# Cubesat_Potencia_Controle-rev3.net
KiCad netlist of a schematic drawn in EAGLE
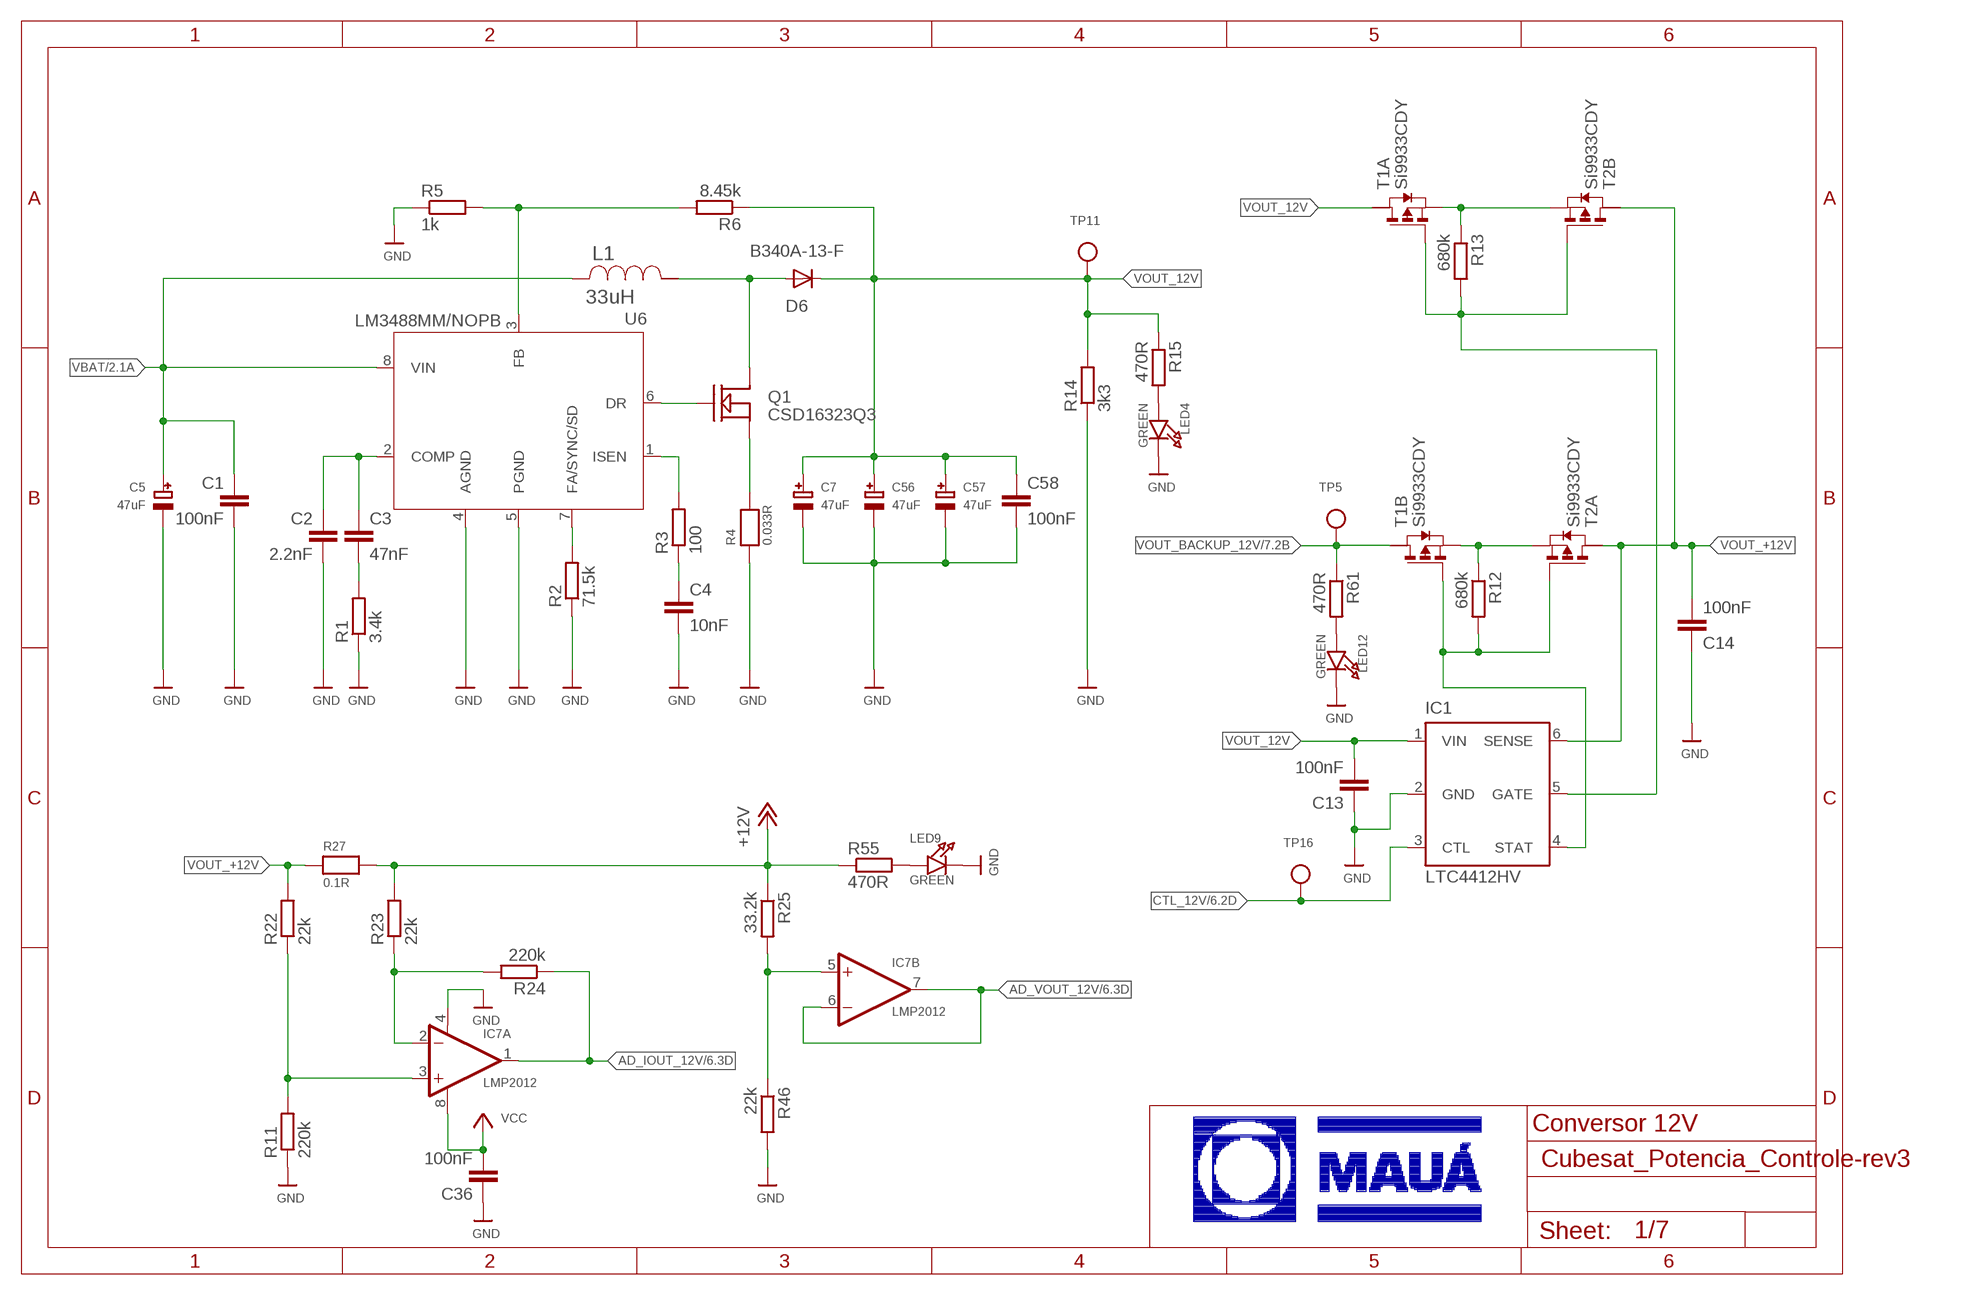
[diagram p0: schematic, sheet 1]
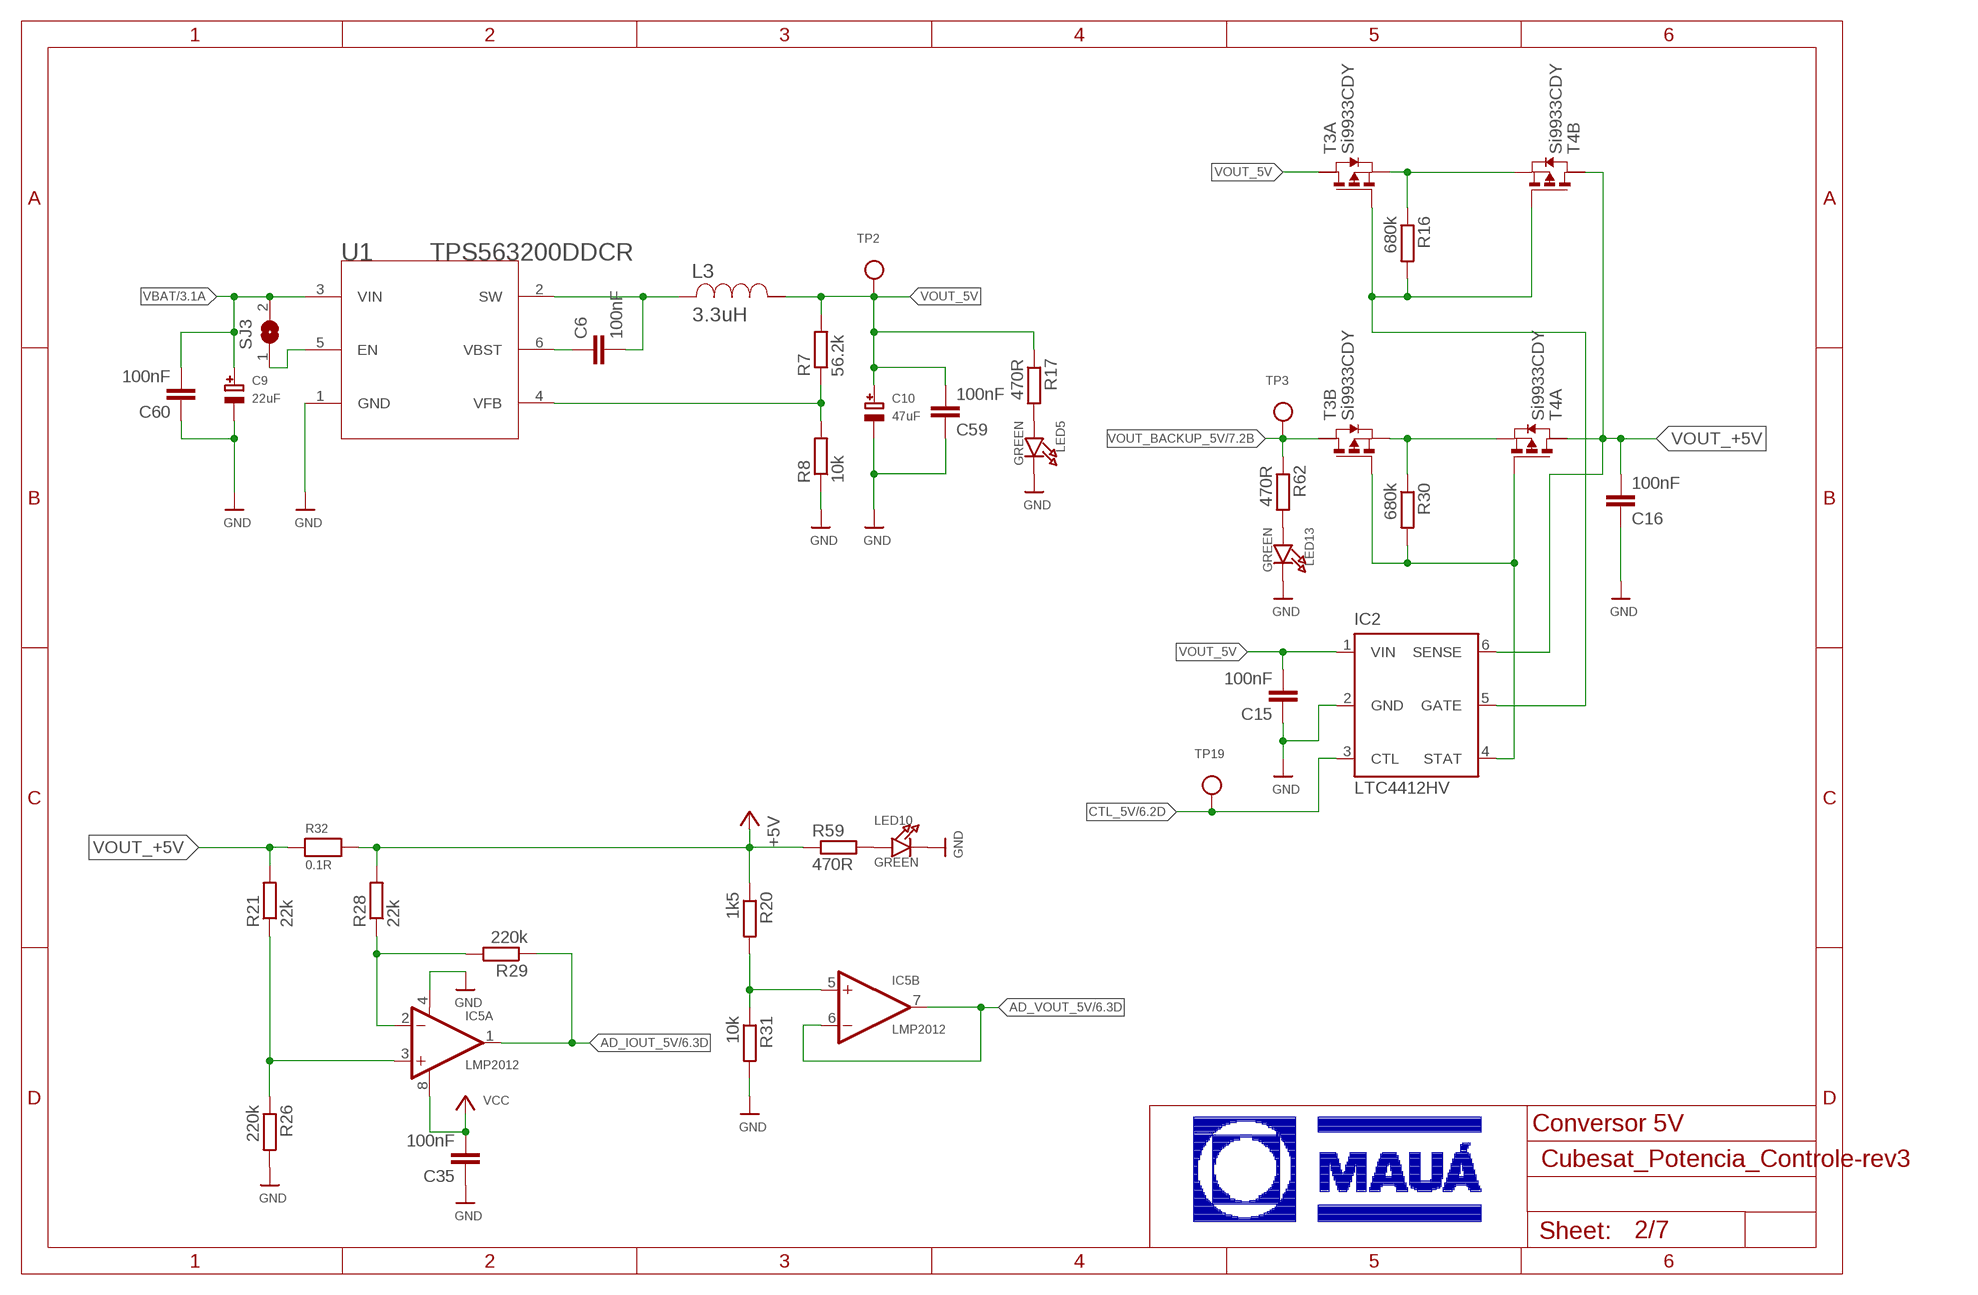
[diagram p1: schematic, sheet 2]
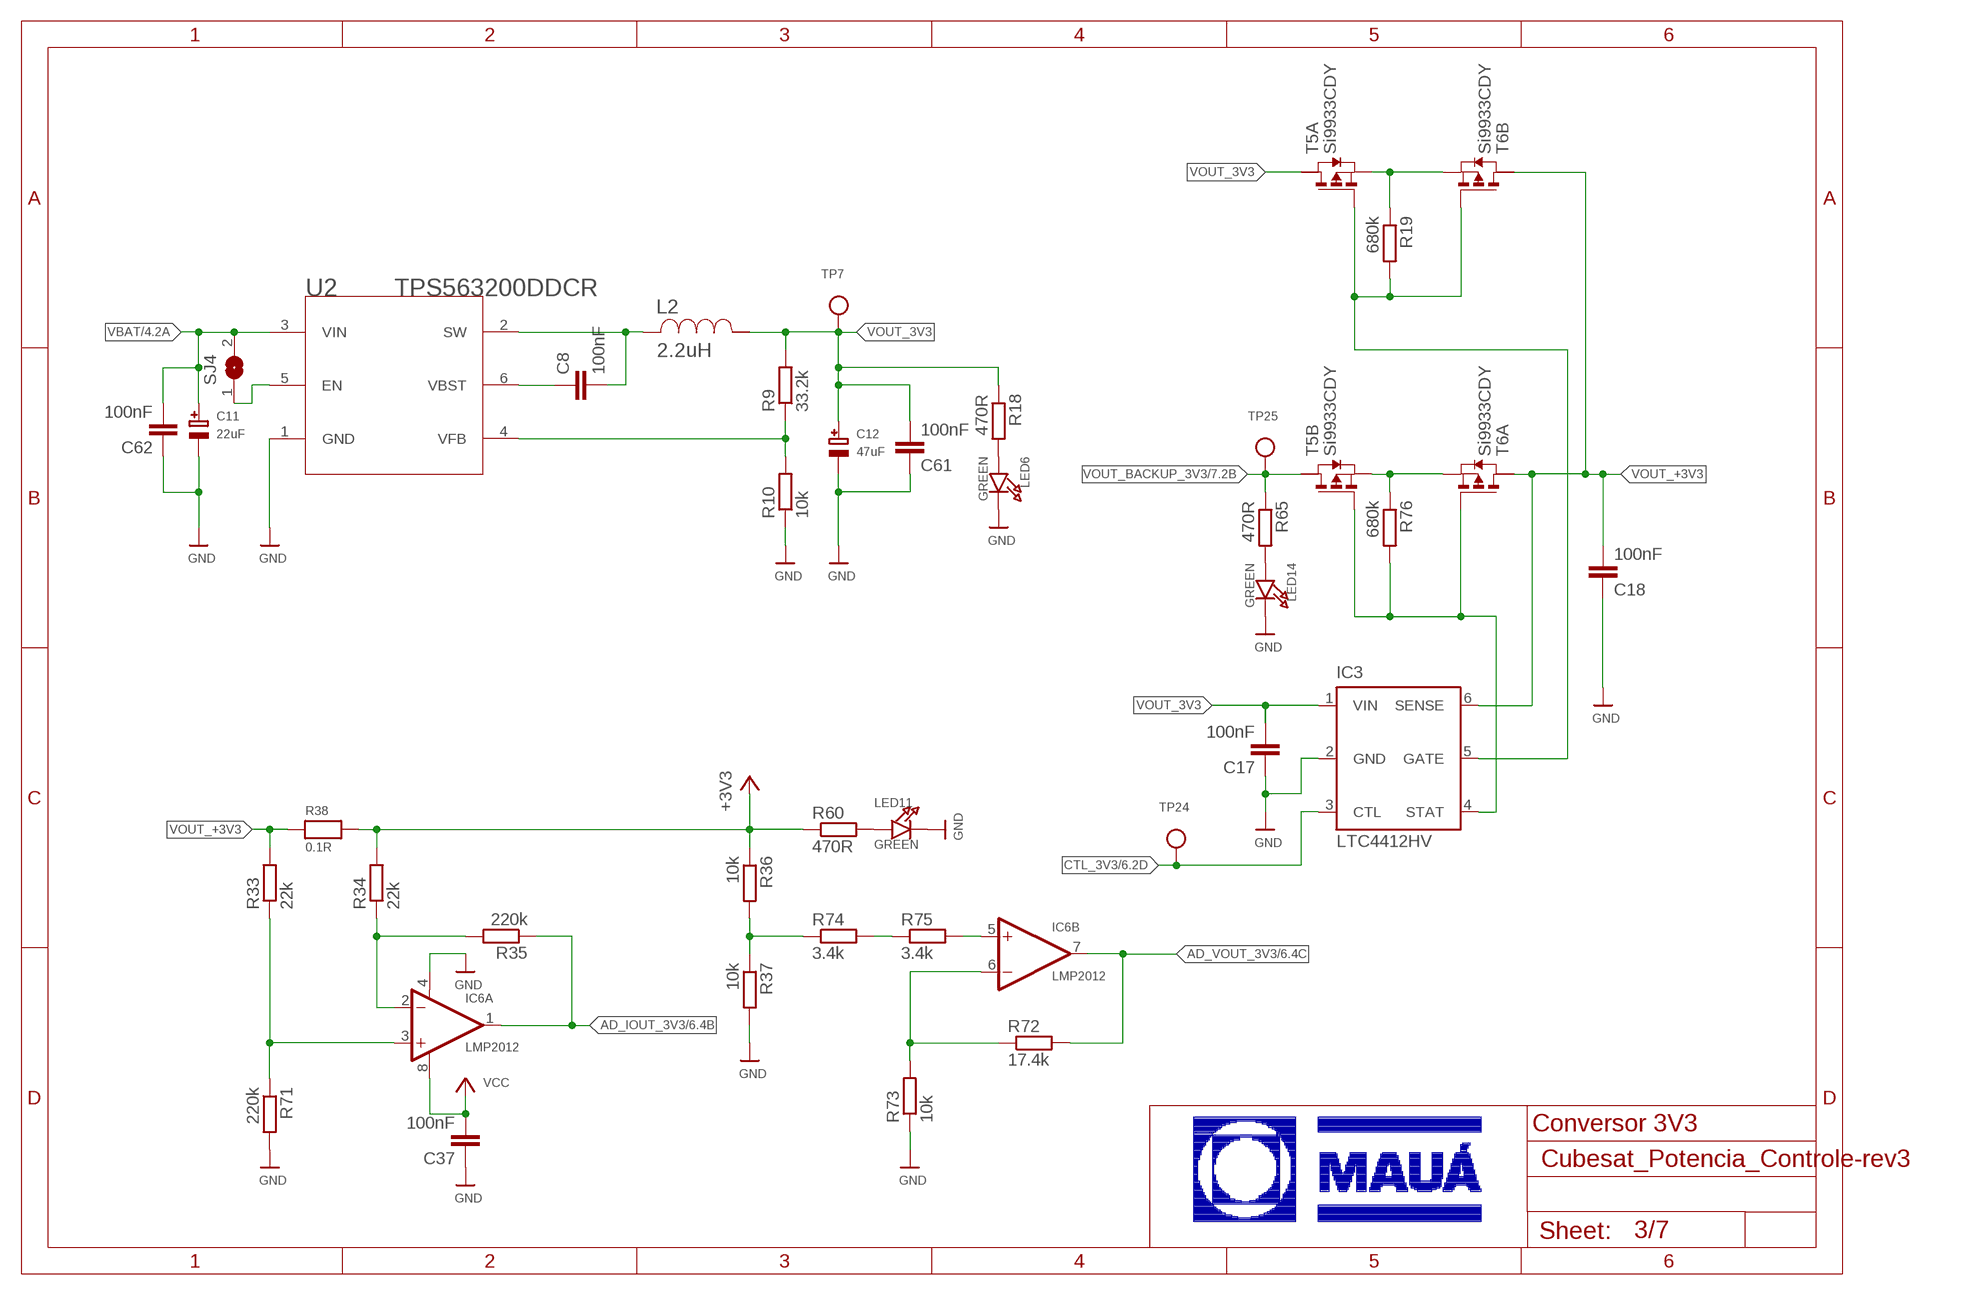
[diagram p2: schematic, sheet 3]
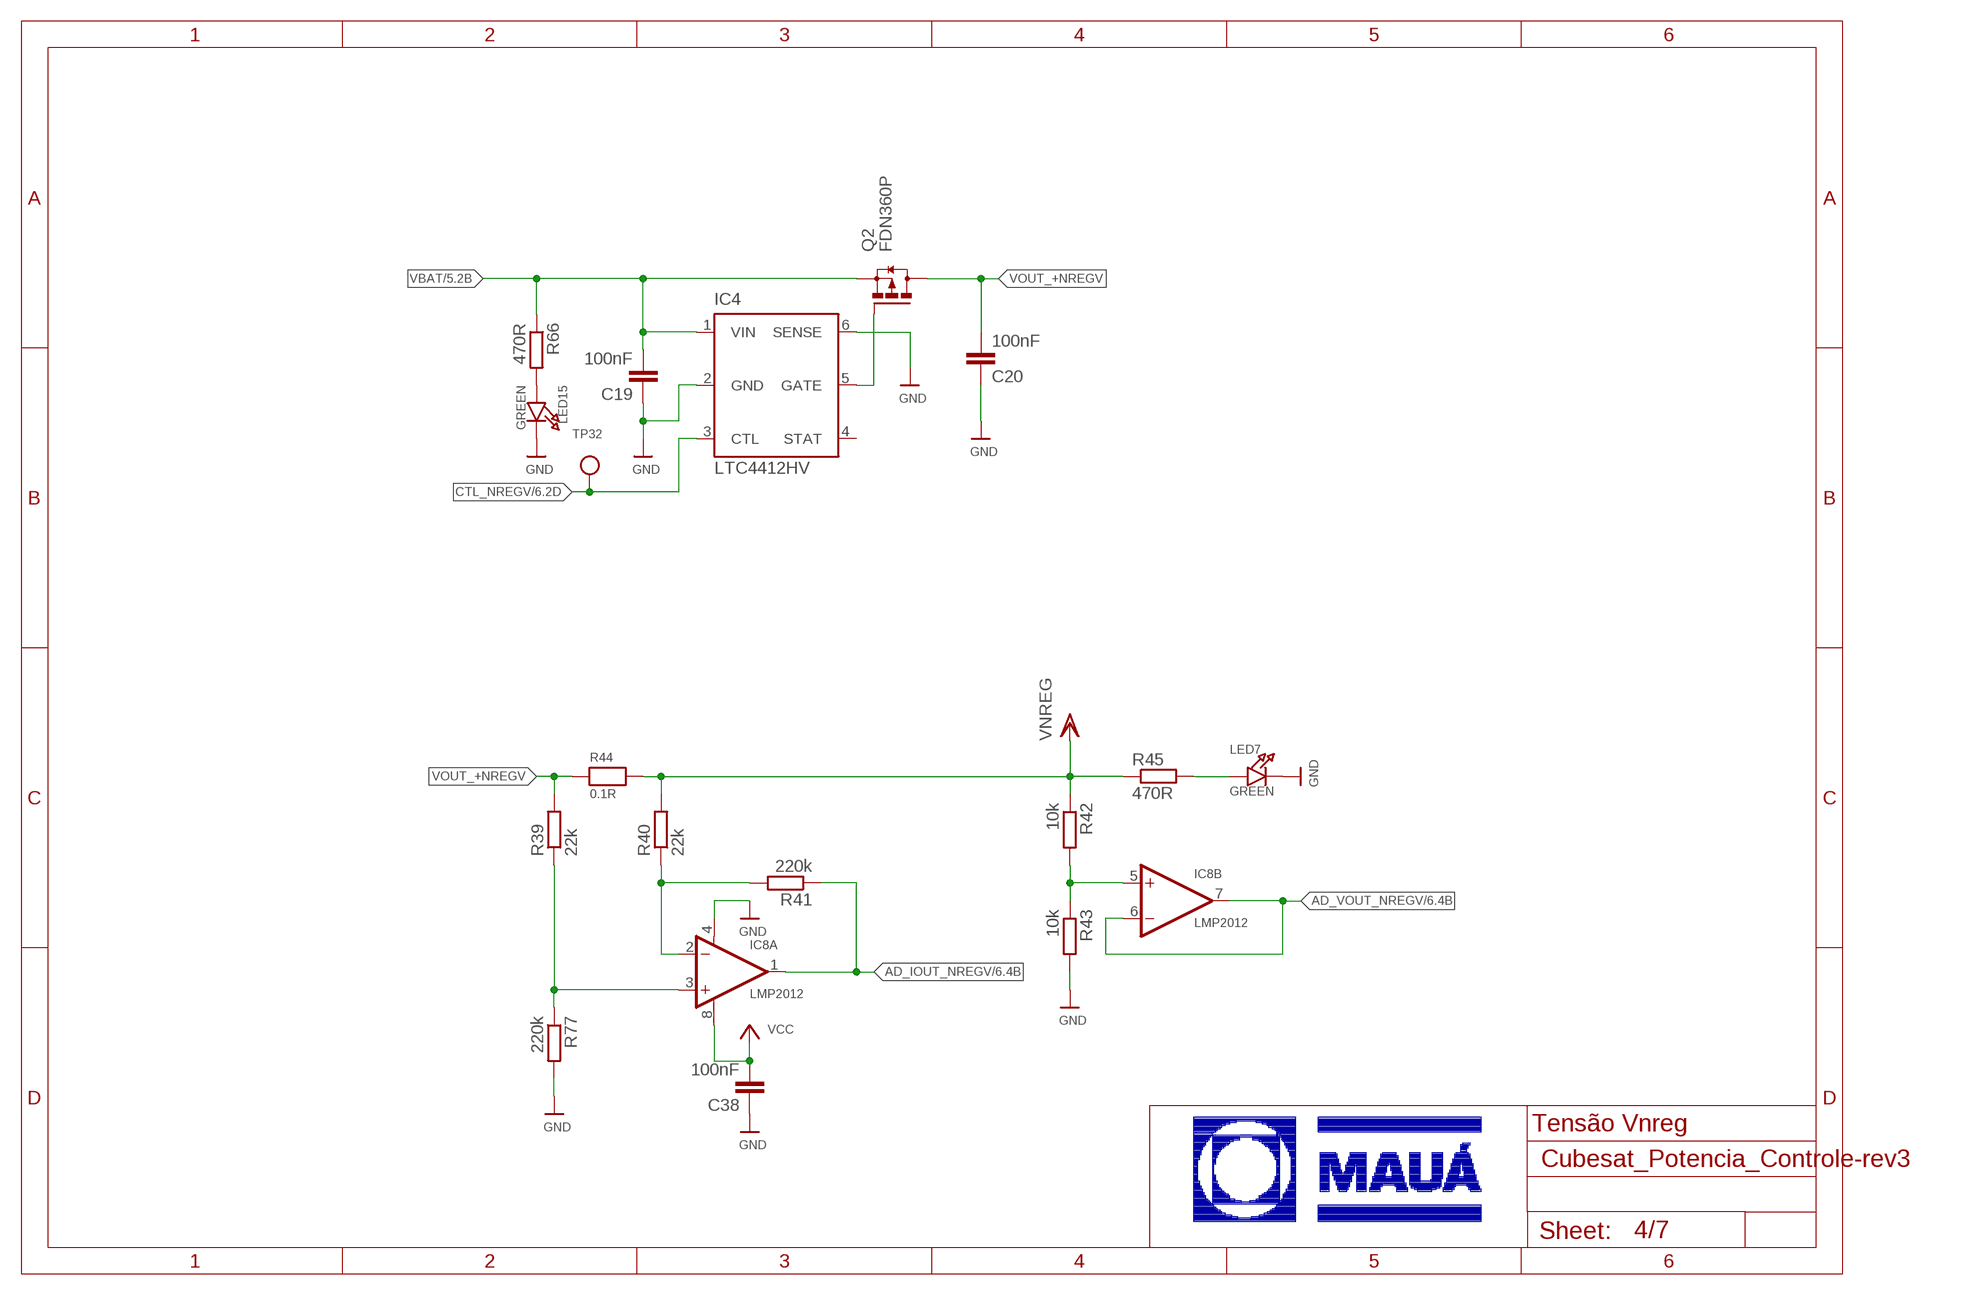
[diagram p3: schematic, sheet 4]
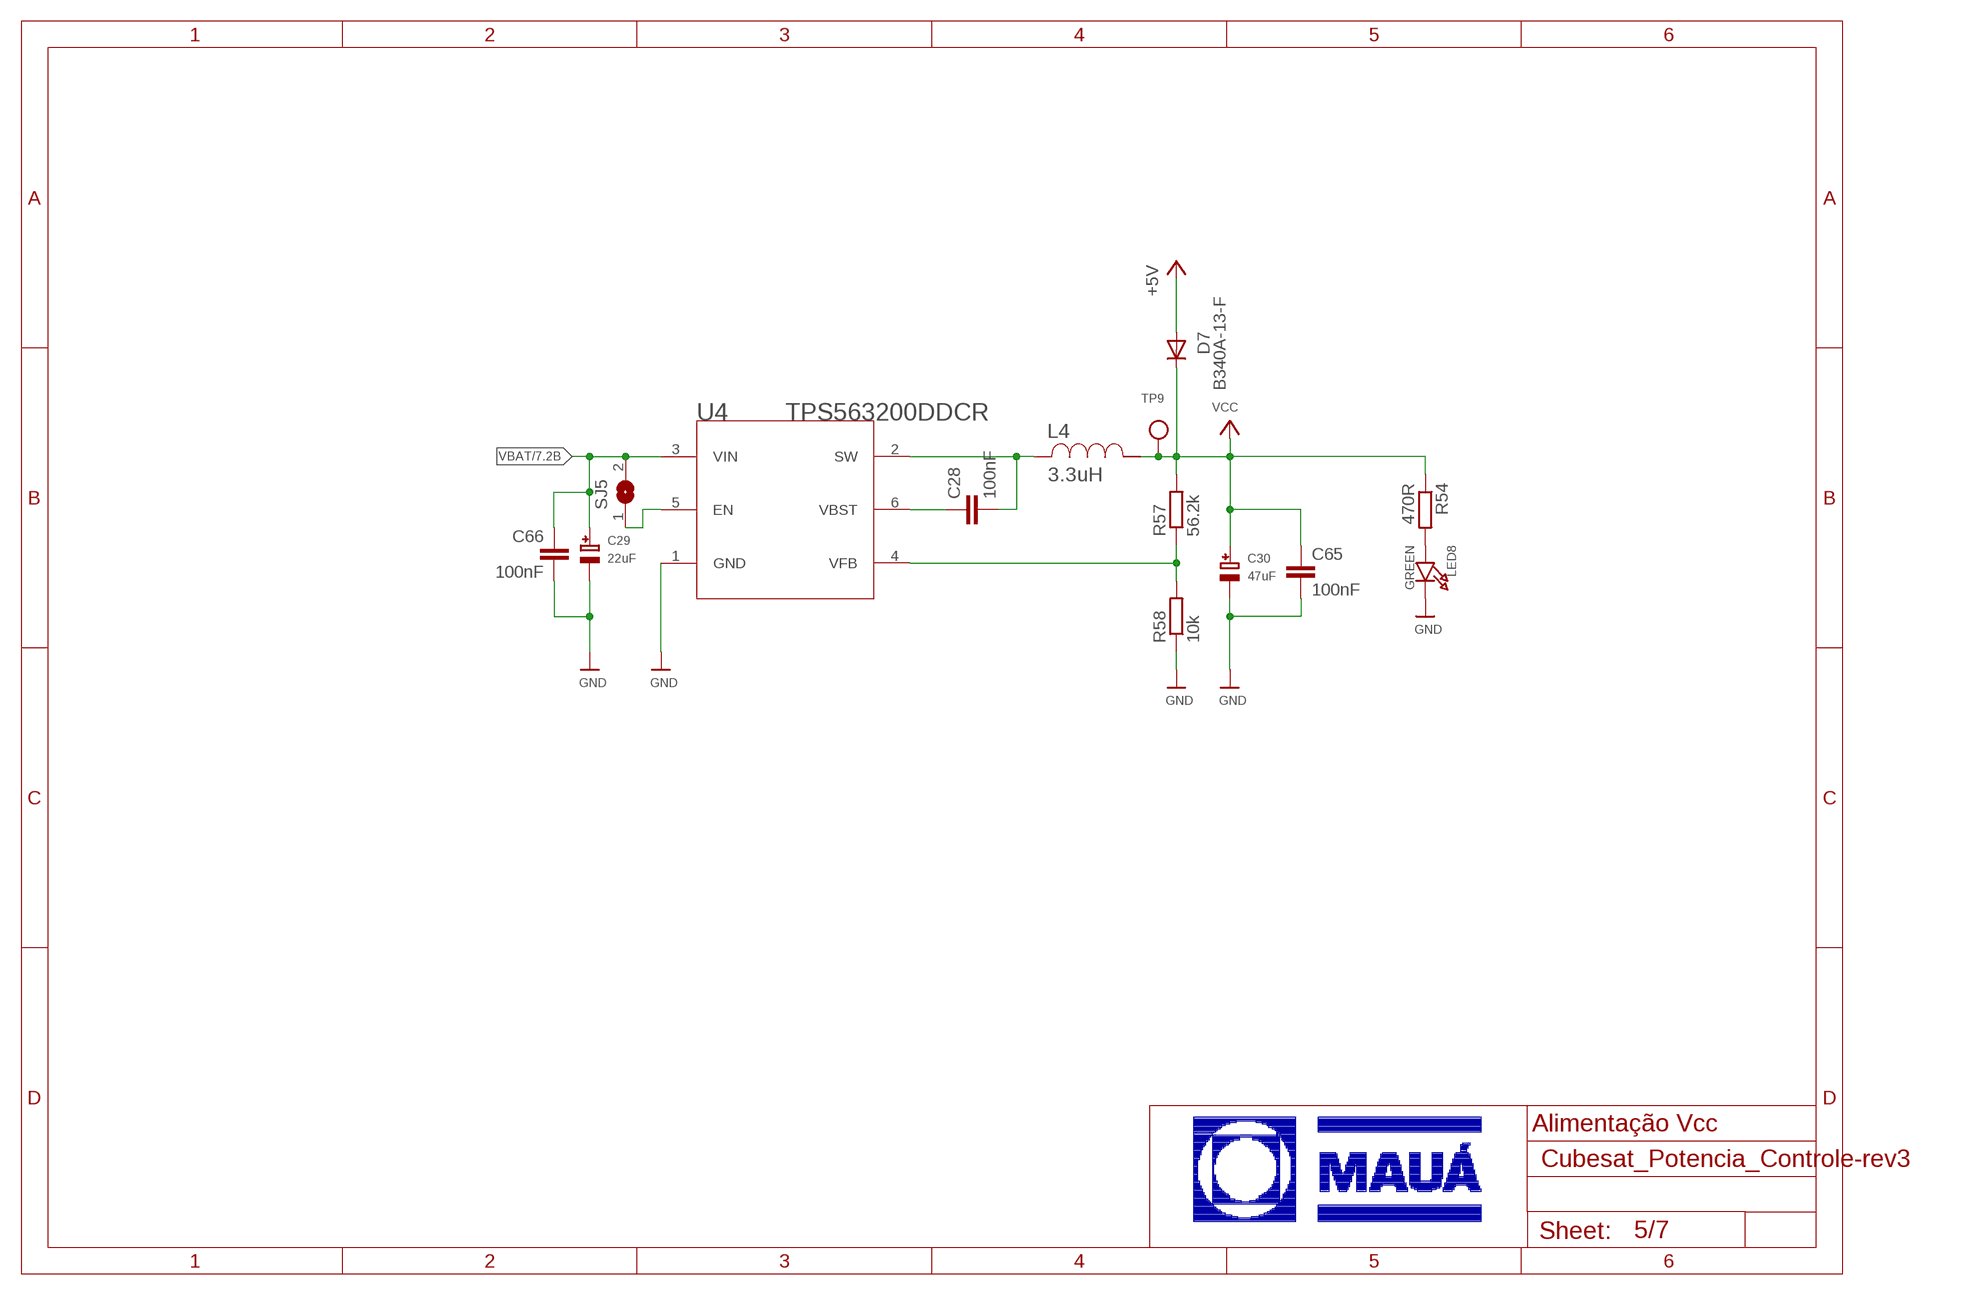
[diagram p4: schematic, sheet 5]
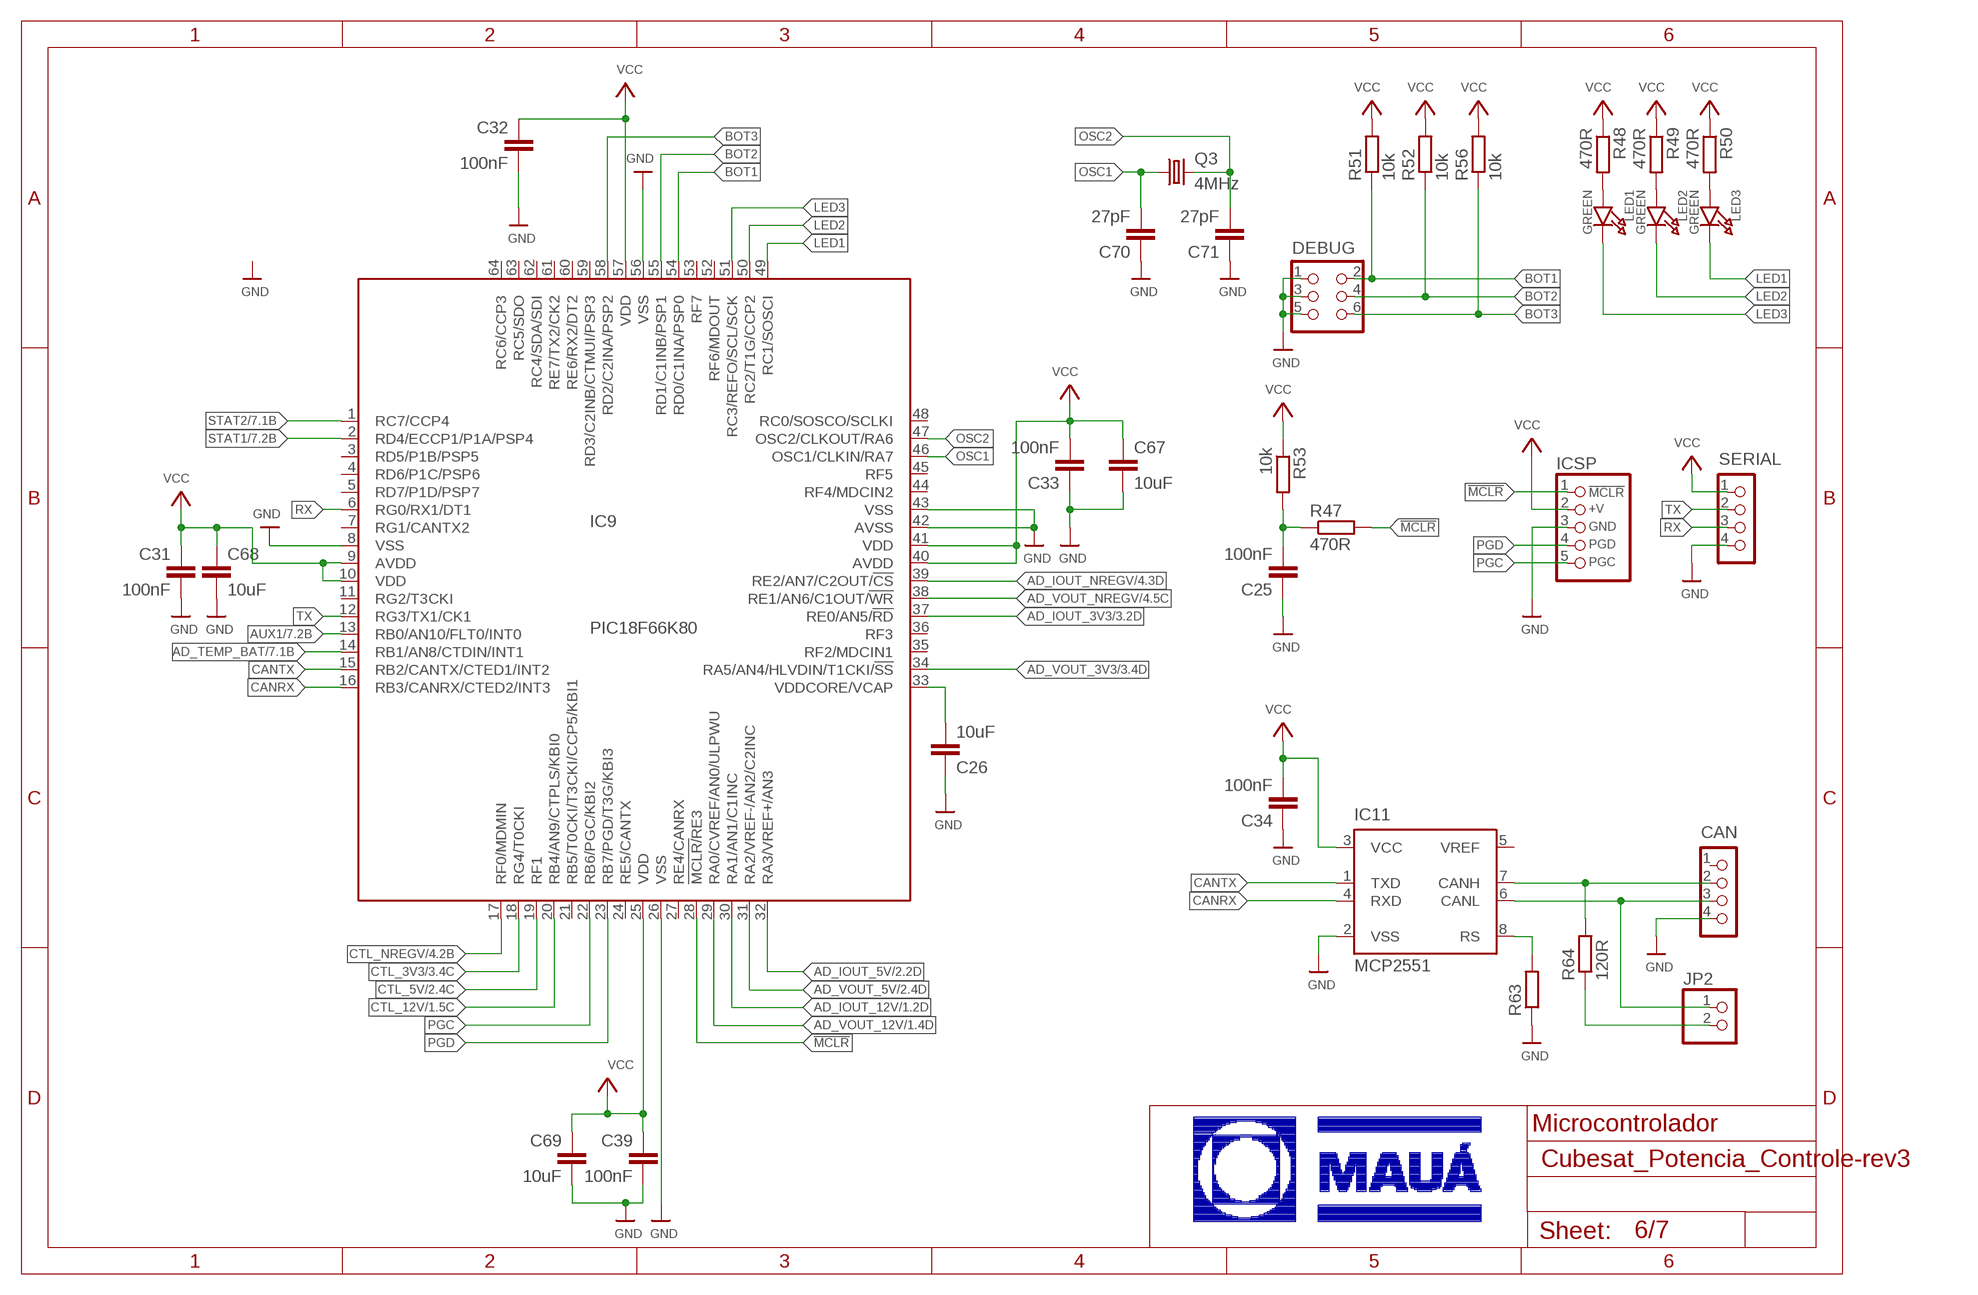
[diagram p5: schematic, sheet 6]
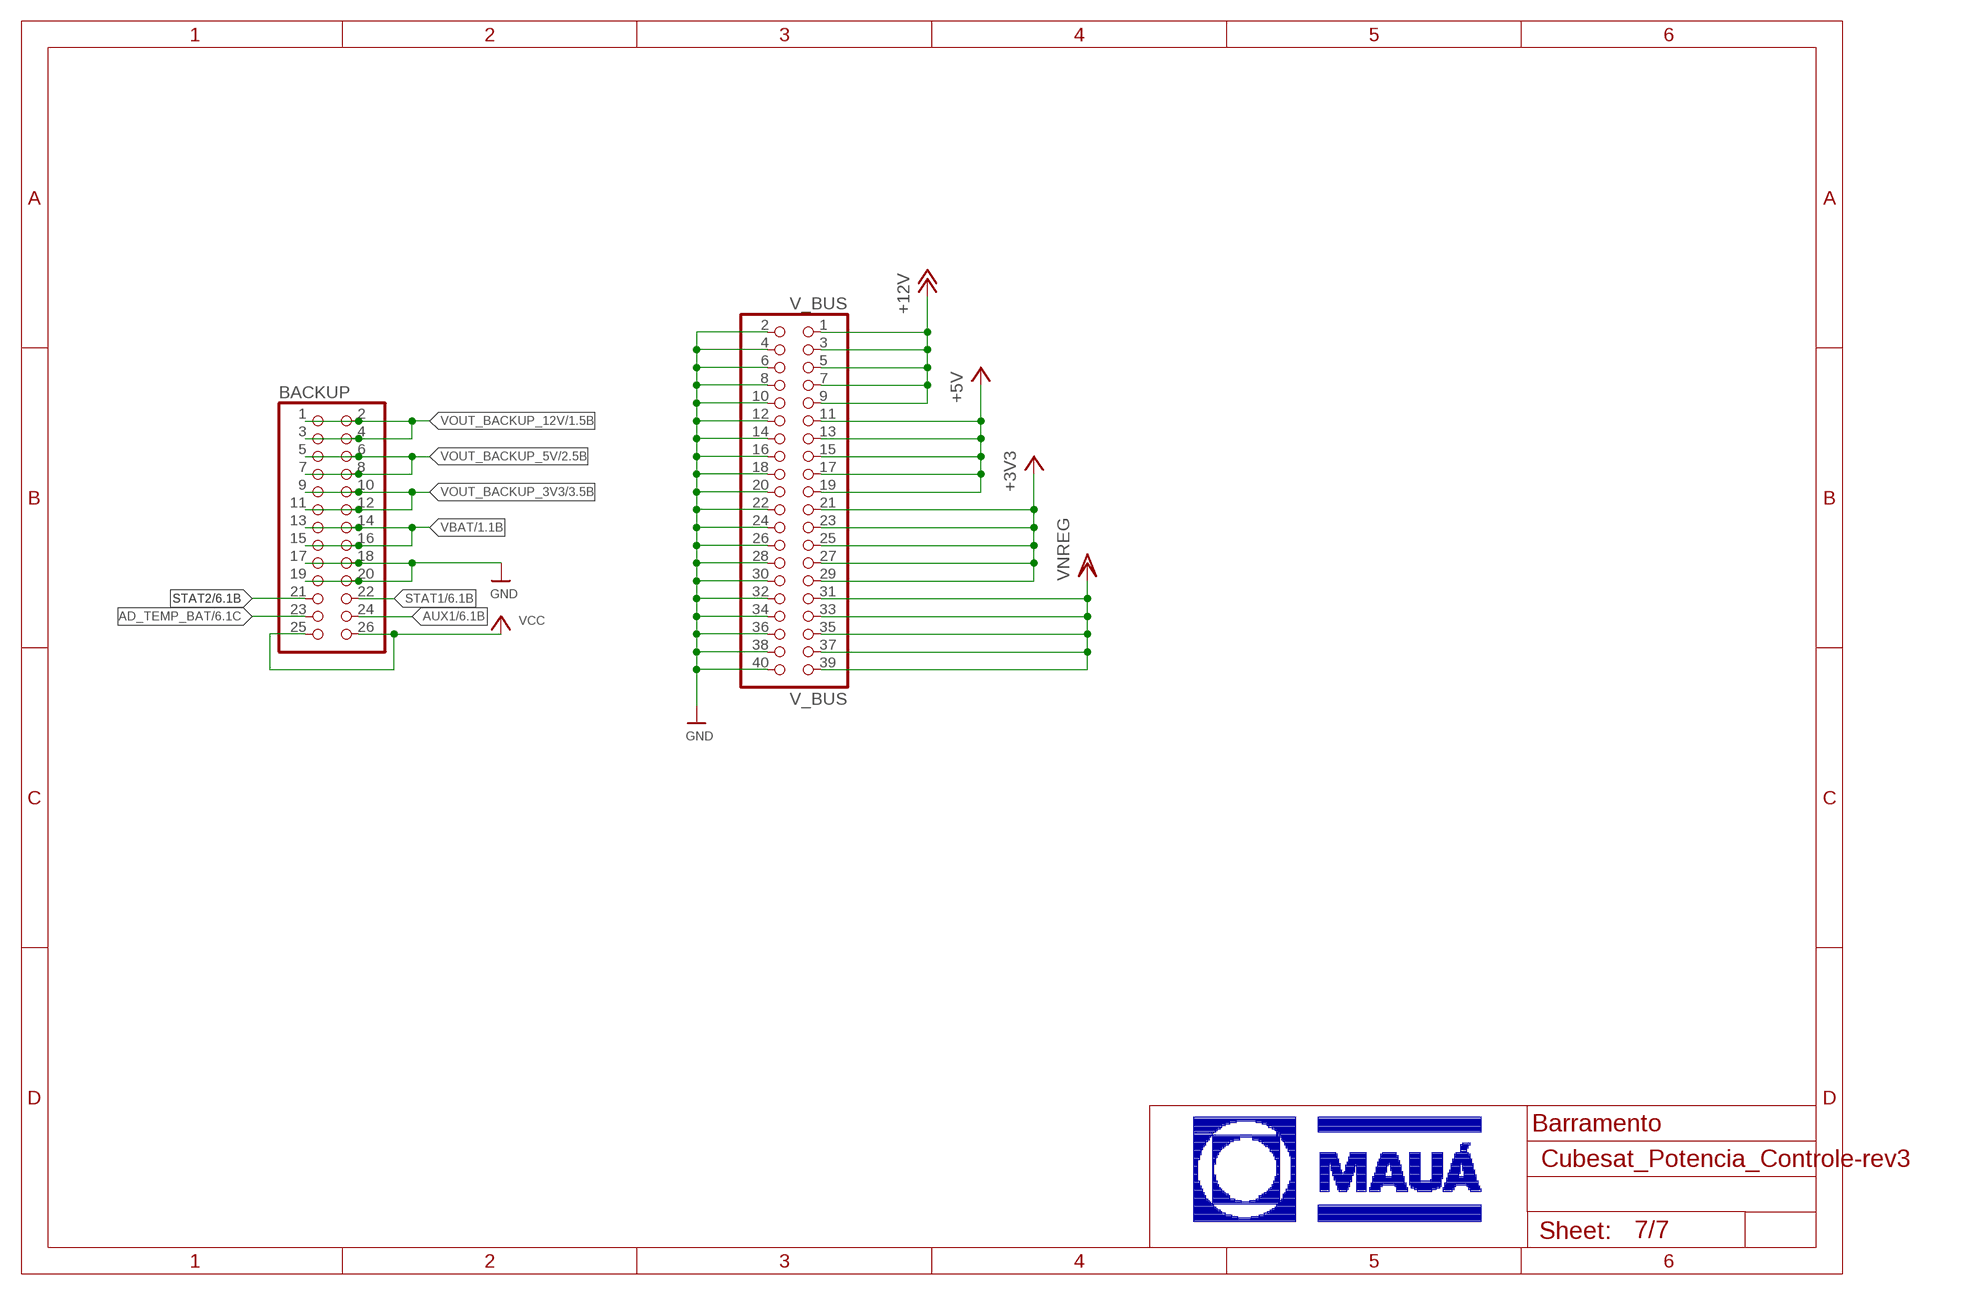
[diagram p6: schematic, sheet 7]

(export (version "E")
  (design (tool "Eeschema 10.0.6"))
  (components
    (comp (ref "C8")
      (value "100nF")
      (footprint "eagle-import:C0805")
      (libsource (lib "eagle-import") (part "C-EUC0805"))
    )
    (comp (ref "C11")
      (value "22uF")
      (footprint "eagle-import:EIA6032-28_C-R")
      (libsource (lib "eagle-import") (part "CAP_TANTALUMC/6032_REFLOW"))
    )
    (comp (ref "C12")
      (value "47uF")
      (footprint "eagle-import:EIA6032-28_C-R")
      (libsource (lib "eagle-import") (part "CAP_TANTALUMC/6032_REFLOW"))
    )
    (comp (ref "C17")
      (value "100nF")
      (footprint "eagle-import:C0805")
      (libsource (lib "eagle-import") (part "C-EUC0805"))
    )
    (comp (ref "C18")
      (value "100nF")
      (footprint "eagle-import:C0805")
      (libsource (lib "eagle-import") (part "C-EUC0805"))
    )
    (comp (ref "C37")
      (value "100nF")
      (footprint "eagle-import:C0805")
      (libsource (lib "eagle-import") (part "C-EUC0805"))
    )
    (comp (ref "C61")
      (value "100nF")
      (footprint "eagle-import:C0805")
      (libsource (lib "eagle-import") (part "C-EUC0805"))
    )
    (comp (ref "C62")
      (value "100nF")
      (footprint "eagle-import:C0805")
      (libsource (lib "eagle-import") (part "C-EUC0805"))
    )
    (comp (ref "IC3")
      (value "LTC4412HV")
      (footprint "eagle-import:TSOT23-6")
      (libsource (lib "eagle-import") (part "LTC4412HV"))
    )
    (comp (ref "IC6")
      (value "LMP2012")
      (footprint "eagle-import:MSOP08")
      (fields
        (field (name "MF") "TEXAS INSTRUMENTS")
        (field (name "MPN") "OPA2237EA/250")
        (field (name "MPN_1") "OPA2237EA/250")
        (field (name "OC_FARNELL") "1470365")
        (field (name "OC_NEWARK") "35C1853")
      )
      (libsource (lib "eagle-import") (part "OPA2237E"))
    )
    (comp (ref "L2")
      (value "2.2uH")
      (footprint "eagle-import:SRR6038")
      (fields (field (name "MANUFACTURER_PART_NUMBER") "SRR6038-3R3Y"))
      (libsource (lib "eagle-import") (part "SRR6038-3R3Y"))
    )
    (comp (ref "LED6")
      (value "GREEN")
      (footprint "eagle-import:CHIPLED_0805")
      (libsource (lib "eagle-import") (part "LED0805"))
    )
    (comp (ref "LED11")
      (value "GREEN")
      (footprint "eagle-import:CHIPLED_0805")
      (libsource (lib "eagle-import") (part "LED0805"))
    )
    (comp (ref "LED14")
      (value "GREEN")
      (footprint "eagle-import:CHIPLED_0805")
      (libsource (lib "eagle-import") (part "LED0805"))
    )
    (comp (ref "R9")
      (value "33.2k")
      (footprint "eagle-import:M0805")
      (libsource (lib "eagle-import") (part "R-EU_M0805"))
    )
    (comp (ref "R10")
      (value "10k")
      (footprint "eagle-import:M0805")
      (libsource (lib "eagle-import") (part "R-EU_M0805"))
    )
    (comp (ref "R18")
      (value "470R")
      (footprint "eagle-import:M0805")
      (libsource (lib "eagle-import") (part "R-EU_M0805"))
    )
    (comp (ref "R19")
      (value "680k")
      (footprint "eagle-import:M0805")
      (libsource (lib "eagle-import") (part "R-EU_M0805"))
    )
    (comp (ref "R33")
      (value "22k")
      (footprint "eagle-import:M0805")
      (libsource (lib "eagle-import") (part "R-EU_M0805"))
    )
    (comp (ref "R34")
      (value "22k")
      (footprint "eagle-import:M0805")
      (libsource (lib "eagle-import") (part "R-EU_M0805"))
    )
    (comp (ref "R35")
      (value "220k")
      (footprint "eagle-import:M0805")
      (libsource (lib "eagle-import") (part "R-EU_M0805"))
    )
    (comp (ref "R36")
      (value "10k")
      (footprint "eagle-import:M0805")
      (libsource (lib "eagle-import") (part "R-EU_M0805"))
    )
    (comp (ref "R37")
      (value "10k")
      (footprint "eagle-import:M0805")
      (libsource (lib "eagle-import") (part "R-EU_M0805"))
    )
    (comp (ref "R38")
      (value "0.1R")
      (footprint "eagle-import:_2818")
      (libsource (lib "eagle-import") (part "RESISTOR2818"))
    )
    (comp (ref "R60")
      (value "470R")
      (footprint "eagle-import:M0805")
      (libsource (lib "eagle-import") (part "R-EU_M0805"))
    )
    (comp (ref "R65")
      (value "470R")
      (footprint "eagle-import:M0805")
      (libsource (lib "eagle-import") (part "R-EU_M0805"))
    )
    (comp (ref "R71")
      (value "220k")
      (footprint "eagle-import:M0805")
      (libsource (lib "eagle-import") (part "R-EU_M0805"))
    )
    (comp (ref "R72")
      (value "17.4k")
      (footprint "eagle-import:M0805")
      (libsource (lib "eagle-import") (part "R-EU_M0805"))
    )
    (comp (ref "R73")
      (value "10k")
      (footprint "eagle-import:M0805")
      (libsource (lib "eagle-import") (part "R-EU_M0805"))
    )
    (comp (ref "R74")
      (value "3.4k")
      (footprint "eagle-import:M0805")
      (libsource (lib "eagle-import") (part "R-EU_M0805"))
    )
    (comp (ref "R75")
      (value "3.4k")
      (footprint "eagle-import:M0805")
      (libsource (lib "eagle-import") (part "R-EU_M0805"))
    )
    (comp (ref "R76")
      (value "680k")
      (footprint "eagle-import:M0805")
      (libsource (lib "eagle-import") (part "R-EU_M0805"))
    )
    (comp (ref "SJ4")
      (value "SOLDERJUMPER")
      (footprint "eagle-import:SOLDERJUMPER_ARROW_NOPASTE")
      (libsource (lib "eagle-import") (part "SOLDERJUMPER"))
    )
    (comp (ref "T5")
      (value "Si9933CDY")
      (footprint "eagle-import:SO8")
      (libsource (lib "eagle-import") (part "PMOS2SO8"))
    )
    (comp (ref "T6")
      (value "Si9933CDY")
      (footprint "eagle-import:SO8")
      (libsource (lib "eagle-import") (part "PMOS2SO8"))
    )
    (comp (ref "TP7")
      (value "TESTPOINT0.1\"")
      (footprint "eagle-import:1X01_ROUND")
      (fields (field (name "BOM") "EXCLUDE"))
      (libsource (lib "eagle-import") (part "TESTPOINT0.1{dblquote}"))
    )
    (comp (ref "TP24")
      (value "TESTPOINT0.1\"")
      (footprint "eagle-import:1X01_ROUND")
      (fields (field (name "BOM") "EXCLUDE"))
      (libsource (lib "eagle-import") (part "TESTPOINT0.1{dblquote}"))
    )
    (comp (ref "TP25")
      (value "TESTPOINT0.1\"")
      (footprint "eagle-import:1X01_ROUND")
      (fields (field (name "BOM") "EXCLUDE"))
      (libsource (lib "eagle-import") (part "TESTPOINT0.1{dblquote}"))
    )
    (comp (ref "U2")
      (value "TPS563200DDCR")
      (footprint "eagle-import:DDC0006A")
      (fields
        (field (name "MANUFACTURER") "Texas Instruments")
        (field (name "PARTNUMBER") "TPS563200DDC")
        (field (name "APPROVEDBY") "Not shown in title block")
        (field (name "AUTHOR") "Not shown in title block")
        (field (name "CHECKEDBY") "Not shown in title block")
        (field (name "ENGINEER") "Not shown in title block")
        (field (name "MODIFIEDDATE") "Not shown in title block")
        (field (name "PUBLISHER") "Texas Instruments")
        (field (name "SYMBOLCREATOR") "a0411947")
      )
      (libsource (lib "eagle-import") (part "TPS563200DDCR"))
    )
    (comp (ref "C28")
      (value "100nF")
      (footprint "eagle-import:C0805")
      (libsource (lib "eagle-import") (part "C-EUC0805"))
    )
    (comp (ref "C29")
      (value "22uF")
      (footprint "eagle-import:EIA6032-28_C-R")
      (libsource (lib "eagle-import") (part "CAP_TANTALUMC/6032_REFLOW"))
    )
    (comp (ref "C30")
      (value "47uF")
      (footprint "eagle-import:EIA6032-28_C-R")
      (libsource (lib "eagle-import") (part "CAP_TANTALUMC/6032_REFLOW"))
    )
    (comp (ref "C65")
      (value "100nF")
      (footprint "eagle-import:C0805")
      (libsource (lib "eagle-import") (part "C-EUC0805"))
    )
    (comp (ref "C66")
      (value "100nF")
      (footprint "eagle-import:C0805")
      (libsource (lib "eagle-import") (part "C-EUC0805"))
    )
    (comp (ref "D7")
      (value "B340A-13-F")
      (footprint "eagle-import:DO214AC")
      (libsource (lib "eagle-import") (part "DIODE-DO214AC"))
    )
    (comp (ref "L4")
      (value "3.3uH")
      (footprint "eagle-import:SRR6038")
      (fields (field (name "MANUFACTURER_PART_NUMBER") "SRR6038-3R3Y"))
      (libsource (lib "eagle-import") (part "SRR6038-3R3Y"))
    )
    (comp (ref "LED8")
      (value "GREEN")
      (footprint "eagle-import:CHIPLED_0805")
      (libsource (lib "eagle-import") (part "LED0805"))
    )
    (comp (ref "R54")
      (value "470R")
      (footprint "eagle-import:M0805")
      (libsource (lib "eagle-import") (part "R-EU_M0805"))
    )
    (comp (ref "R57")
      (value "56.2k")
      (footprint "eagle-import:M0805")
      (libsource (lib "eagle-import") (part "R-EU_M0805"))
    )
    (comp (ref "R58")
      (value "10k")
      (footprint "eagle-import:M0805")
      (libsource (lib "eagle-import") (part "R-EU_M0805"))
    )
    (comp (ref "SJ5")
      (value "SOLDERJUMPER")
      (footprint "eagle-import:SOLDERJUMPER_ARROW_NOPASTE")
      (libsource (lib "eagle-import") (part "SOLDERJUMPER"))
    )
    (comp (ref "TP9")
      (value "TESTPOINT0.1\"")
      (footprint "eagle-import:1X01_ROUND")
      (fields (field (name "BOM") "EXCLUDE"))
      (libsource (lib "eagle-import") (part "TESTPOINT0.1{dblquote}"))
    )
    (comp (ref "U4")
      (value "TPS563200DDCR")
      (footprint "eagle-import:DDC0006A")
      (fields
        (field (name "MANUFACTURER") "Texas Instruments")
        (field (name "PARTNUMBER") "TPS563200DDC")
        (field (name "APPROVEDBY") "Not shown in title block")
        (field (name "AUTHOR") "Not shown in title block")
        (field (name "CHECKEDBY") "Not shown in title block")
        (field (name "ENGINEER") "Not shown in title block")
        (field (name "MODIFIEDDATE") "Not shown in title block")
        (field (name "PUBLISHER") "Texas Instruments")
        (field (name "SYMBOLCREATOR") "a0411947")
      )
      (libsource (lib "eagle-import") (part "TPS563200DDCR"))
    )
    (comp (ref "C19")
      (value "100nF")
      (footprint "eagle-import:C0805")
      (libsource (lib "eagle-import") (part "C-EUC0805"))
    )
    (comp (ref "C20")
      (value "100nF")
      (footprint "eagle-import:C0805")
      (libsource (lib "eagle-import") (part "C-EUC0805"))
    )
    (comp (ref "C38")
      (value "100nF")
      (footprint "eagle-import:C0805")
      (libsource (lib "eagle-import") (part "C-EUC0805"))
    )
    (comp (ref "IC4")
      (value "LTC4412HV")
      (footprint "eagle-import:TSOT23-6")
      (libsource (lib "eagle-import") (part "LTC4412HV"))
    )
    (comp (ref "IC8")
      (value "LMP2012")
      (footprint "eagle-import:MSOP08")
      (fields
        (field (name "MF") "TEXAS INSTRUMENTS")
        (field (name "MPN") "OPA2237EA/250")
        (field (name "MPN_1") "OPA2237EA/250")
        (field (name "OC_FARNELL") "1470365")
        (field (name "OC_NEWARK") "35C1853")
      )
      (libsource (lib "eagle-import") (part "OPA2237E"))
    )
    (comp (ref "LED7")
      (value "GREEN")
      (footprint "eagle-import:CHIPLED_0805")
      (libsource (lib "eagle-import") (part "LED0805"))
    )
    (comp (ref "LED15")
      (value "GREEN")
      (footprint "eagle-import:CHIPLED_0805")
      (libsource (lib "eagle-import") (part "LED0805"))
    )
    (comp (ref "Q2")
      (value "FDN360P")
      (footprint "eagle-import:SUPER-SOT3")
      (libsource (lib "eagle-import") (part "FDN360P"))
    )
    (comp (ref "R39")
      (value "22k")
      (footprint "eagle-import:M0805")
      (libsource (lib "eagle-import") (part "R-EU_M0805"))
    )
    (comp (ref "R40")
      (value "22k")
      (footprint "eagle-import:M0805")
      (libsource (lib "eagle-import") (part "R-EU_M0805"))
    )
    (comp (ref "R41")
      (value "220k")
      (footprint "eagle-import:M0805")
      (libsource (lib "eagle-import") (part "R-EU_M0805"))
    )
    (comp (ref "R42")
      (value "10k")
      (footprint "eagle-import:M0805")
      (libsource (lib "eagle-import") (part "R-EU_M0805"))
    )
    (comp (ref "R43")
      (value "10k")
      (footprint "eagle-import:M0805")
      (libsource (lib "eagle-import") (part "R-EU_M0805"))
    )
    (comp (ref "R44")
      (value "0.1R")
      (footprint "eagle-import:_2818")
      (libsource (lib "eagle-import") (part "RESISTOR2818"))
    )
    (comp (ref "R45")
      (value "470R")
      (footprint "eagle-import:M0805")
      (libsource (lib "eagle-import") (part "R-EU_M0805"))
    )
    (comp (ref "R66")
      (value "470R")
      (footprint "eagle-import:M0805")
      (libsource (lib "eagle-import") (part "R-EU_M0805"))
    )
    (comp (ref "R77")
      (value "220k")
      (footprint "eagle-import:M0805")
      (libsource (lib "eagle-import") (part "R-EU_M0805"))
    )
    (comp (ref "TP32")
      (value "TESTPOINT0.1\"")
      (footprint "eagle-import:1X01_ROUND")
      (fields (field (name "BOM") "EXCLUDE"))
      (libsource (lib "eagle-import") (part "TESTPOINT0.1{dblquote}"))
    )
    (comp (ref "C1")
      (value "100nF")
      (footprint "eagle-import:C0805")
      (libsource (lib "eagle-import") (part "C-EUC0805"))
    )
    (comp (ref "C2")
      (value "2.2nF")
      (footprint "eagle-import:C0805")
      (libsource (lib "eagle-import") (part "C-EUC0805"))
    )
    (comp (ref "C3")
      (value "47nF")
      (footprint "eagle-import:C0805")
      (libsource (lib "eagle-import") (part "C-EUC0805"))
    )
    (comp (ref "C4")
      (value "10nF")
      (footprint "eagle-import:C0805")
      (libsource (lib "eagle-import") (part "C-EUC0805"))
    )
    (comp (ref "C5")
      (value "47uF")
      (footprint "eagle-import:EIA6032-28_C-R")
      (libsource (lib "eagle-import") (part "CAP_TANTALUMC/6032_REFLOW"))
    )
    (comp (ref "C7")
      (value "47uF")
      (footprint "eagle-import:EIA6032-28_C-R")
      (libsource (lib "eagle-import") (part "CAP_TANTALUMC/6032_REFLOW"))
    )
    (comp (ref "C13")
      (value "100nF")
      (footprint "eagle-import:C0805")
      (libsource (lib "eagle-import") (part "C-EUC0805"))
    )
    (comp (ref "C14")
      (value "100nF")
      (footprint "eagle-import:C0805")
      (libsource (lib "eagle-import") (part "C-EUC0805"))
    )
    (comp (ref "C36")
      (value "100nF")
      (footprint "eagle-import:C0805")
      (libsource (lib "eagle-import") (part "C-EUC0805"))
    )
    (comp (ref "C56")
      (value "47uF")
      (footprint "eagle-import:EIA6032-28_C-R")
      (libsource (lib "eagle-import") (part "CAP_TANTALUMC/6032_REFLOW"))
    )
    (comp (ref "C57")
      (value "47uF")
      (footprint "eagle-import:EIA6032-28_C-R")
      (libsource (lib "eagle-import") (part "CAP_TANTALUMC/6032_REFLOW"))
    )
    (comp (ref "C58")
      (value "100nF")
      (footprint "eagle-import:C0805")
      (libsource (lib "eagle-import") (part "C-EUC0805"))
    )
    (comp (ref "D6")
      (value "B340A-13-F")
      (footprint "eagle-import:DO214AC")
      (libsource (lib "eagle-import") (part "DIODE-DO214AC"))
    )
    (comp (ref "IC1")
      (value "LTC4412HV")
      (footprint "eagle-import:TSOT23-6")
      (libsource (lib "eagle-import") (part "LTC4412HV"))
    )
    (comp (ref "IC7")
      (value "LMP2012")
      (footprint "eagle-import:MSOP08")
      (fields
        (field (name "MF") "TEXAS INSTRUMENTS")
        (field (name "MPN") "OPA2237EA/250")
        (field (name "MPN_1") "OPA2237EA/250")
        (field (name "OC_FARNELL") "1470365")
        (field (name "OC_NEWARK") "35C1853")
      )
      (libsource (lib "eagle-import") (part "OPA2237E"))
    )
    (comp (ref "L1")
      (value "33uH")
      (footprint "eagle-import:SDR1307")
      (fields (field (name "MANUFACTURER_PART_NUMBER") "SDR1307-330KL"))
      (libsource (lib "eagle-import") (part "SDR1307-330KL"))
    )
    (comp (ref "LED4")
      (value "GREEN")
      (footprint "eagle-import:CHIPLED_0805")
      (libsource (lib "eagle-import") (part "LED0805"))
    )
    (comp (ref "LED9")
      (value "GREEN")
      (footprint "eagle-import:CHIPLED_0805")
      (libsource (lib "eagle-import") (part "LED0805"))
    )
    (comp (ref "LED12")
      (value "GREEN")
      (footprint "eagle-import:CHIPLED_0805")
      (libsource (lib "eagle-import") (part "LED0805"))
    )
    (comp (ref "Q1")
      (value "CSD16323Q3")
      (footprint "eagle-import:TRANS_NEXFET_Q3")
      (libsource (lib "eagle-import") (part "CSD16323Q3"))
    )
    (comp (ref "R1")
      (value "3.4k")
      (footprint "eagle-import:M0805")
      (libsource (lib "eagle-import") (part "R-EU_M0805"))
    )
    (comp (ref "R2")
      (value "71.5k")
      (footprint "eagle-import:M0805")
      (libsource (lib "eagle-import") (part "R-EU_M0805"))
    )
    (comp (ref "R3")
      (value "100")
      (footprint "eagle-import:M0805")
      (libsource (lib "eagle-import") (part "R-EU_M0805"))
    )
    (comp (ref "R4")
      (value "0.033R")
      (footprint "eagle-import:_2818")
      (libsource (lib "eagle-import") (part "RESISTOR2818"))
    )
    (comp (ref "R5")
      (value "1k")
      (footprint "eagle-import:M0805")
      (libsource (lib "eagle-import") (part "R-EU_M0805"))
    )
    (comp (ref "R6")
      (value "8.45k")
      (footprint "eagle-import:M0805")
      (libsource (lib "eagle-import") (part "R-EU_M0805"))
    )
    (comp (ref "R11")
      (value "220k")
      (footprint "eagle-import:M0805")
      (libsource (lib "eagle-import") (part "R-EU_M0805"))
    )
    (comp (ref "R12")
      (value "680k")
      (footprint "eagle-import:M0805")
      (libsource (lib "eagle-import") (part "R-EU_M0805"))
    )
    (comp (ref "R13")
      (value "680k")
      (footprint "eagle-import:M0805")
      (libsource (lib "eagle-import") (part "R-EU_M0805"))
    )
    (comp (ref "R14")
      (value "3k3")
      (footprint "eagle-import:M0805")
      (libsource (lib "eagle-import") (part "R-EU_M0805"))
    )
    (comp (ref "R15")
      (value "470R")
      (footprint "eagle-import:M0805")
      (libsource (lib "eagle-import") (part "R-EU_M0805"))
    )
    (comp (ref "R22")
      (value "22k")
      (footprint "eagle-import:M0805")
      (libsource (lib "eagle-import") (part "R-EU_M0805"))
    )
    (comp (ref "R23")
      (value "22k")
      (footprint "eagle-import:M0805")
      (libsource (lib "eagle-import") (part "R-EU_M0805"))
    )
    (comp (ref "R24")
      (value "220k")
      (footprint "eagle-import:M0805")
      (libsource (lib "eagle-import") (part "R-EU_M0805"))
    )
    (comp (ref "R25")
      (value "33.2k")
      (footprint "eagle-import:M0805")
      (libsource (lib "eagle-import") (part "R-EU_M0805"))
    )
    (comp (ref "R27")
      (value "0.1R")
      (footprint "eagle-import:_2818")
      (libsource (lib "eagle-import") (part "RESISTOR2818"))
    )
    (comp (ref "R46")
      (value "22k")
      (footprint "eagle-import:M0805")
      (libsource (lib "eagle-import") (part "R-EU_M0805"))
    )
    (comp (ref "R55")
      (value "470R")
      (footprint "eagle-import:M0805")
      (libsource (lib "eagle-import") (part "R-EU_M0805"))
    )
    (comp (ref "R61")
      (value "470R")
      (footprint "eagle-import:M0805")
      (libsource (lib "eagle-import") (part "R-EU_M0805"))
    )
    (comp (ref "T1")
      (value "Si9933CDY")
      (footprint "eagle-import:SO8")
      (libsource (lib "eagle-import") (part "PMOS2SO8"))
    )
    (comp (ref "T2")
      (value "Si9933CDY")
      (footprint "eagle-import:SO8")
      (libsource (lib "eagle-import") (part "PMOS2SO8"))
    )
    (comp (ref "TP5")
      (value "TESTPOINT0.1\"")
      (footprint "eagle-import:1X01_ROUND")
      (fields (field (name "BOM") "EXCLUDE"))
      (libsource (lib "eagle-import") (part "TESTPOINT0.1{dblquote}"))
    )
    (comp (ref "TP11")
      (value "TESTPOINT0.1\"")
      (footprint "eagle-import:1X01_ROUND")
      (fields (field (name "BOM") "EXCLUDE"))
      (libsource (lib "eagle-import") (part "TESTPOINT0.1{dblquote}"))
    )
    (comp (ref "TP16")
      (value "TESTPOINT0.1\"")
      (footprint "eagle-import:1X01_ROUND")
      (fields (field (name "BOM") "EXCLUDE"))
      (libsource (lib "eagle-import") (part "TESTPOINT0.1{dblquote}"))
    )
    (comp (ref "U6")
      (value "LM3488MM/NOPB")
      (footprint "eagle-import:MUA08A")
      (libsource (lib "eagle-import") (part "LM3488MM/NOPB"))
    )
    (comp (ref "BACKUP")
      (value "HEADER-2X13")
      (footprint "eagle-import:2X13")
      (libsource (lib "eagle-import") (part "HEADER-2X13"))
    )
    (comp (ref "V_BUS")
      (value "V_BUS")
      (footprint "eagle-import:2X20")
      (libsource (lib "eagle-import") (part "PINHD-2X20"))
    )
    (comp (ref "C6")
      (value "100nF")
      (footprint "eagle-import:C0805")
      (libsource (lib "eagle-import") (part "C-EUC0805"))
    )
    (comp (ref "C9")
      (value "22uF")
      (footprint "eagle-import:EIA6032-28_C-R")
      (libsource (lib "eagle-import") (part "CAP_TANTALUMC/6032_REFLOW"))
    )
    (comp (ref "C10")
      (value "47uF")
      (footprint "eagle-import:EIA6032-28_C-R")
      (libsource (lib "eagle-import") (part "CAP_TANTALUMC/6032_REFLOW"))
    )
    (comp (ref "C15")
      (value "100nF")
      (footprint "eagle-import:C0805")
      (libsource (lib "eagle-import") (part "C-EUC0805"))
    )
    (comp (ref "C16")
      (value "100nF")
      (footprint "eagle-import:C0805")
      (libsource (lib "eagle-import") (part "C-EUC0805"))
    )
    (comp (ref "C35")
      (value "100nF")
      (footprint "eagle-import:C0805")
      (libsource (lib "eagle-import") (part "C-EUC0805"))
    )
    (comp (ref "C59")
      (value "100nF")
      (footprint "eagle-import:C0805")
      (libsource (lib "eagle-import") (part "C-EUC0805"))
    )
    (comp (ref "C60")
      (value "100nF")
      (footprint "eagle-import:C0805")
      (libsource (lib "eagle-import") (part "C-EUC0805"))
    )
    (comp (ref "IC2")
      (value "LTC4412HV")
      (footprint "eagle-import:TSOT23-6")
      (libsource (lib "eagle-import") (part "LTC4412HV"))
    )
    (comp (ref "IC5")
      (value "LMP2012")
      (footprint "eagle-import:MSOP08")
      (fields
        (field (name "MF") "TEXAS INSTRUMENTS")
        (field (name "MPN") "OPA2237EA/250")
        (field (name "MPN_1") "OPA2237EA/250")
        (field (name "OC_FARNELL") "1470365")
        (field (name "OC_NEWARK") "35C1853")
      )
      (libsource (lib "eagle-import") (part "OPA2237E"))
    )
    (comp (ref "L3")
      (value "3.3uH")
      (footprint "eagle-import:SRR6038")
      (fields (field (name "MANUFACTURER_PART_NUMBER") "SRR6038-3R3Y"))
      (libsource (lib "eagle-import") (part "SRR6038-3R3Y"))
    )
    (comp (ref "LED5")
      (value "GREEN")
      (footprint "eagle-import:CHIPLED_0805")
      (libsource (lib "eagle-import") (part "LED0805"))
    )
    (comp (ref "LED10")
      (value "GREEN")
      (footprint "eagle-import:CHIPLED_0805")
      (libsource (lib "eagle-import") (part "LED0805"))
    )
    (comp (ref "LED13")
      (value "GREEN")
      (footprint "eagle-import:CHIPLED_0805")
      (libsource (lib "eagle-import") (part "LED0805"))
    )
    (comp (ref "R7")
      (value "56.2k")
      (footprint "eagle-import:M0805")
      (libsource (lib "eagle-import") (part "R-EU_M0805"))
    )
    (comp (ref "R8")
      (value "10k")
      (footprint "eagle-import:M0805")
      (libsource (lib "eagle-import") (part "R-EU_M0805"))
    )
    (comp (ref "R16")
      (value "680k")
      (footprint "eagle-import:M0805")
      (libsource (lib "eagle-import") (part "R-EU_M0805"))
    )
    (comp (ref "R17")
      (value "470R")
      (footprint "eagle-import:M0805")
      (libsource (lib "eagle-import") (part "R-EU_M0805"))
    )
    (comp (ref "R20")
      (value "1k5")
      (footprint "eagle-import:M0805")
      (libsource (lib "eagle-import") (part "R-EU_M0805"))
    )
    (comp (ref "R21")
      (value "22k")
      (footprint "eagle-import:M0805")
      (libsource (lib "eagle-import") (part "R-EU_M0805"))
    )
    (comp (ref "R26")
      (value "220k")
      (footprint "eagle-import:M0805")
      (libsource (lib "eagle-import") (part "R-EU_M0805"))
    )
    (comp (ref "R28")
      (value "22k")
      (footprint "eagle-import:M0805")
      (libsource (lib "eagle-import") (part "R-EU_M0805"))
    )
    (comp (ref "R29")
      (value "220k")
      (footprint "eagle-import:M0805")
      (libsource (lib "eagle-import") (part "R-EU_M0805"))
    )
    (comp (ref "R30")
      (value "680k")
      (footprint "eagle-import:M0805")
      (libsource (lib "eagle-import") (part "R-EU_M0805"))
    )
    (comp (ref "R31")
      (value "10k")
      (footprint "eagle-import:M0805")
      (libsource (lib "eagle-import") (part "R-EU_M0805"))
    )
    (comp (ref "R32")
      (value "0.1R")
      (footprint "eagle-import:_2818")
      (libsource (lib "eagle-import") (part "RESISTOR2818"))
    )
    (comp (ref "R59")
      (value "470R")
      (footprint "eagle-import:M0805")
      (libsource (lib "eagle-import") (part "R-EU_M0805"))
    )
    (comp (ref "R62")
      (value "470R")
      (footprint "eagle-import:M0805")
      (libsource (lib "eagle-import") (part "R-EU_M0805"))
    )
    (comp (ref "SJ3")
      (value "SOLDERJUMPER")
      (footprint "eagle-import:SOLDERJUMPER_ARROW_NOPASTE")
      (libsource (lib "eagle-import") (part "SOLDERJUMPER"))
    )
    (comp (ref "T3")
      (value "Si9933CDY")
      (footprint "eagle-import:SO8")
      (libsource (lib "eagle-import") (part "PMOS2SO8"))
    )
    (comp (ref "T4")
      (value "Si9933CDY")
      (footprint "eagle-import:SO8")
      (libsource (lib "eagle-import") (part "PMOS2SO8"))
    )
    (comp (ref "TP2")
      (value "TESTPOINT0.1\"")
      (footprint "eagle-import:1X01_ROUND")
      (fields (field (name "BOM") "EXCLUDE"))
      (libsource (lib "eagle-import") (part "TESTPOINT0.1{dblquote}"))
    )
    (comp (ref "TP3")
      (value "TESTPOINT0.1\"")
      (footprint "eagle-import:1X01_ROUND")
      (fields (field (name "BOM") "EXCLUDE"))
      (libsource (lib "eagle-import") (part "TESTPOINT0.1{dblquote}"))
    )
    (comp (ref "TP19")
      (value "TESTPOINT0.1\"")
      (footprint "eagle-import:1X01_ROUND")
      (fields (field (name "BOM") "EXCLUDE"))
      (libsource (lib "eagle-import") (part "TESTPOINT0.1{dblquote}"))
    )
    (comp (ref "U1")
      (value "TPS563200DDCR")
      (footprint "eagle-import:DDC0006A")
      (fields
        (field (name "MANUFACTURER") "Texas Instruments")
        (field (name "PARTNUMBER") "TPS563200DDC")
        (field (name "APPROVEDBY") "Not shown in title block")
        (field (name "AUTHOR") "Not shown in title block")
        (field (name "CHECKEDBY") "Not shown in title block")
        (field (name "ENGINEER") "Not shown in title block")
        (field (name "MODIFIEDDATE") "Not shown in title block")
        (field (name "PUBLISHER") "Texas Instruments")
        (field (name "SYMBOLCREATOR") "a0411947")
      )
      (libsource (lib "eagle-import") (part "TPS563200DDCR"))
    )
    (comp (ref "C25")
      (value "100nF")
      (footprint "eagle-import:C0805")
      (libsource (lib "eagle-import") (part "C-EUC0805"))
    )
    (comp (ref "C26")
      (value "10uF")
      (footprint "eagle-import:C0805")
      (libsource (lib "eagle-import") (part "C-EUC0805"))
    )
    (comp (ref "C31")
      (value "100nF")
      (footprint "eagle-import:C0805")
      (libsource (lib "eagle-import") (part "C-EUC0805"))
    )
    (comp (ref "C32")
      (value "100nF")
      (footprint "eagle-import:C0805")
      (libsource (lib "eagle-import") (part "C-EUC0805"))
    )
    (comp (ref "C33")
      (value "100nF")
      (footprint "eagle-import:C0805")
      (libsource (lib "eagle-import") (part "C-EUC0805"))
    )
    (comp (ref "C34")
      (value "100nF")
      (footprint "eagle-import:C0805")
      (libsource (lib "eagle-import") (part "C-EUC0805"))
    )
    (comp (ref "C39")
      (value "100nF")
      (footprint "eagle-import:C0805")
      (libsource (lib "eagle-import") (part "C-EUC0805"))
    )
    (comp (ref "C67")
      (value "10uF")
      (footprint "eagle-import:C0805")
      (libsource (lib "eagle-import") (part "C-EUC0805"))
    )
    (comp (ref "C68")
      (value "10uF")
      (footprint "eagle-import:C0805")
      (libsource (lib "eagle-import") (part "C-EUC0805"))
    )
    (comp (ref "C69")
      (value "10uF")
      (footprint "eagle-import:C0805")
      (libsource (lib "eagle-import") (part "C-EUC0805"))
    )
    (comp (ref "C70")
      (value "27pF")
      (footprint "eagle-import:C0805")
      (libsource (lib "eagle-import") (part "C-EUC0805"))
    )
    (comp (ref "C71")
      (value "27pF")
      (footprint "eagle-import:C0805")
      (libsource (lib "eagle-import") (part "C-EUC0805"))
    )
    (comp (ref "CAN")
      (value "CON_HEADER_1X04")
      (footprint "eagle-import:M1X4")
      (libsource (lib "eagle-import") (part "CON_HEADER_1X04"))
    )
    (comp (ref "DEBUG")
      (value "CON_HEADER_2X03-PTH")
      (footprint "eagle-import:M2X3")
      (libsource (lib "eagle-import") (part "CON_HEADER_2X03-PTH"))
    )
    (comp (ref "IC9")
      (value "PIC18F66K80")
      (footprint "eagle-import:TQFP64-10X10X1MM")
      (libsource (lib "eagle-import") (part "PIC18F66K80"))
    )
    (comp (ref "IC11")
      (value "MCP2551")
      (footprint "eagle-import:SO-08")
      (libsource (lib "eagle-import") (part "MCP2551"))
    )
    (comp (ref "ICSP")
      (value "CON_HEADER_PRG_PIC_ICSP0.1INCH_B")
      (footprint "eagle-import:HEADER_PRG_1X05_ICSP_B")
      (libsource (lib "eagle-import") (part "CON_HEADER_PRG_PIC_ICSP0.1INCH_B"))
    )
    (comp (ref "JP2")
      (value "HEADER-1X2ROUND")
      (footprint "eagle-import:1X02_ROUND")
      (libsource (lib "eagle-import") (part "HEADER-1X2ROUND"))
    )
    (comp (ref "LED1")
      (value "GREEN")
      (footprint "eagle-import:CHIPLED_0805")
      (libsource (lib "eagle-import") (part "LED0805"))
    )
    (comp (ref "LED2")
      (value "GREEN")
      (footprint "eagle-import:CHIPLED_0805")
      (libsource (lib "eagle-import") (part "LED0805"))
    )
    (comp (ref "LED3")
      (value "GREEN")
      (footprint "eagle-import:CHIPLED_0805")
      (libsource (lib "eagle-import") (part "LED0805"))
    )
    (comp (ref "Q3")
      (value "4MHz")
      (footprint "eagle-import:HC49_S")
      (libsource (lib "eagle-import") (part "CRYSTALHC49S"))
    )
    (comp (ref "R47")
      (value "470R")
      (footprint "eagle-import:M0805")
      (libsource (lib "eagle-import") (part "R-EU_M0805"))
    )
    (comp (ref "R48")
      (value "470R")
      (footprint "eagle-import:M0805")
      (libsource (lib "eagle-import") (part "R-EU_M0805"))
    )
    (comp (ref "R49")
      (value "470R")
      (footprint "eagle-import:M0805")
      (libsource (lib "eagle-import") (part "R-EU_M0805"))
    )
    (comp (ref "R50")
      (value "470R")
      (footprint "eagle-import:M0805")
      (libsource (lib "eagle-import") (part "R-EU_M0805"))
    )
    (comp (ref "R51")
      (value "10k")
      (footprint "eagle-import:M0805")
      (libsource (lib "eagle-import") (part "R-EU_M0805"))
    )
    (comp (ref "R52")
      (value "10k")
      (footprint "eagle-import:M0805")
      (libsource (lib "eagle-import") (part "R-EU_M0805"))
    )
    (comp (ref "R53")
      (value "10k")
      (footprint "eagle-import:M0805")
      (libsource (lib "eagle-import") (part "R-EU_M0805"))
    )
    (comp (ref "R56")
      (value "10k")
      (footprint "eagle-import:M0805")
      (libsource (lib "eagle-import") (part "R-EU_M0805"))
    )
    (comp (ref "R63")
      (value "R-EU_M0805")
      (footprint "eagle-import:M0805")
      (libsource (lib "eagle-import") (part "R-EU_M0805"))
    )
    (comp (ref "R64")
      (value "120R")
      (footprint "eagle-import:M0805")
      (libsource (lib "eagle-import") (part "R-EU_M0805"))
    )
    (comp (ref "SERIAL")
      (value "CON_HEADER_1X04")
      (footprint "eagle-import:M1X4")
      (libsource (lib "eagle-import") (part "CON_HEADER_1X04"))
    )
  )
  (nets
    (net (code "1") (name "+3V3") (class "Default")
      (node (ref "R34") (pin "2") (pinfunction "2_2") (pintype "passive"))
      (node (ref "R36") (pin "1") (pinfunction "1_1") (pintype "passive"))
      (node (ref "R38") (pin "2") (pinfunction "2_2") (pintype "passive"))
      (node (ref "R60") (pin "1") (pinfunction "1_1") (pintype "passive"))
      (node (ref "V_BUS") (pin "21") (pinfunction "21_21") (pintype "passive"))
      (node (ref "V_BUS") (pin "23") (pinfunction "23_23") (pintype "passive"))
      (node (ref "V_BUS") (pin "25") (pinfunction "25_25") (pintype "passive"))
      (node (ref "V_BUS") (pin "27") (pinfunction "27_27") (pintype "passive"))
      (node (ref "V_BUS") (pin "29") (pinfunction "29_29") (pintype "passive"))
    )
    (net (code "2") (name "+5V") (class "Default")
      (node (ref "D7") (pin "A") (pinfunction "A_A") (pintype "passive"))
      (node (ref "R20") (pin "1") (pinfunction "1_1") (pintype "passive"))
      (node (ref "R28") (pin "2") (pinfunction "2_2") (pintype "passive"))
      (node (ref "R32") (pin "2") (pinfunction "2_2") (pintype "passive"))
      (node (ref "R59") (pin "1") (pinfunction "1_1") (pintype "passive"))
      (node (ref "V_BUS") (pin "11") (pinfunction "11_11") (pintype "passive"))
      (node (ref "V_BUS") (pin "13") (pinfunction "13_13") (pintype "passive"))
      (node (ref "V_BUS") (pin "15") (pinfunction "15_15") (pintype "passive"))
      (node (ref "V_BUS") (pin "17") (pinfunction "17_17") (pintype "passive"))
      (node (ref "V_BUS") (pin "19") (pinfunction "19_19") (pintype "passive"))
    )
    (net (code "3") (name "+12V") (class "Default")
      (node (ref "R23") (pin "2") (pinfunction "2_2") (pintype "passive"))
      (node (ref "R25") (pin "1") (pinfunction "1_1") (pintype "passive"))
      (node (ref "R27") (pin "2") (pinfunction "2_2") (pintype "passive"))
      (node (ref "R55") (pin "1") (pinfunction "1_1") (pintype "passive"))
      (node (ref "V_BUS") (pin "1") (pinfunction "1_1") (pintype "passive"))
      (node (ref "V_BUS") (pin "3") (pinfunction "3_3") (pintype "passive"))
      (node (ref "V_BUS") (pin "5") (pinfunction "5_5") (pintype "passive"))
      (node (ref "V_BUS") (pin "7") (pinfunction "7_7") (pintype "passive"))
      (node (ref "V_BUS") (pin "9") (pinfunction "9_9") (pintype "passive"))
    )
    (net (code "4") (name "AD_IOUT_3V3") (class "Default")
      (node (ref "IC6") (pin "1") (pinfunction "OUT_1") (pintype "output"))
      (node (ref "IC9") (pin "37") (pinfunction "RE0/AN5/~{RD}_37") (pintype "input"))
      (node (ref "R35") (pin "1") (pinfunction "1_1") (pintype "passive"))
    )
    (net (code "5") (name "AD_IOUT_5V") (class "Default")
      (node (ref "IC5") (pin "1") (pinfunction "OUT_1") (pintype "output"))
      (node (ref "IC9") (pin "32") (pinfunction "RA3/VREF+/AN3_32") (pintype "bidirectional"))
      (node (ref "R29") (pin "1") (pinfunction "1_1") (pintype "passive"))
    )
    (net (code "6") (name "AD_IOUT_12V") (class "Default")
      (node (ref "IC7") (pin "1") (pinfunction "OUT_1") (pintype "output"))
      (node (ref "IC9") (pin "30") (pinfunction "RA1/AN1/C1INC_30") (pintype "bidirectional"))
      (node (ref "R24") (pin "1") (pinfunction "1_1") (pintype "passive"))
    )
    (net (code "7") (name "AD_IOUT_NREGV") (class "Default")
      (node (ref "IC8") (pin "1") (pinfunction "OUT_1") (pintype "output"))
      (node (ref "IC9") (pin "39") (pinfunction "RE2/AN7/C2OUT/~{CS}_39") (pintype "bidirectional"))
      (node (ref "R41") (pin "1") (pinfunction "1_1") (pintype "passive"))
    )
    (net (code "8") (name "AD_TEMP_BAT") (class "Default")
      (node (ref "BACKUP") (pin "23") (pinfunction "23_23") (pintype "passive"))
      (node (ref "IC9") (pin "14") (pinfunction "RB1/AN8/CTDIN/INT1_14") (pintype "bidirectional"))
    )
    (net (code "9") (name "AD_VOUT_3V3") (class "Default")
      (node (ref "IC6") (pin "7") (pinfunction "OUT_7") (pintype "output"))
      (node (ref "IC9") (pin "34") (pinfunction "RA5/AN4/HLVDIN/T1CKI/~{SS}_34") (pintype "bidirectional"))
      (node (ref "R72") (pin "2") (pinfunction "2_2") (pintype "passive"))
    )
    (net (code "10") (name "AD_VOUT_5V") (class "Default")
      (node (ref "IC5") (pin "6") (pinfunction "-IN_6") (pintype "input"))
      (node (ref "IC5") (pin "7") (pinfunction "OUT_7") (pintype "output"))
      (node (ref "IC9") (pin "31") (pinfunction "RA2/VREF-/AN2/C2INC_31") (pintype "bidirectional"))
    )
    (net (code "11") (name "AD_VOUT_12V") (class "Default")
      (node (ref "IC7") (pin "6") (pinfunction "-IN_6") (pintype "input"))
      (node (ref "IC7") (pin "7") (pinfunction "OUT_7") (pintype "output"))
      (node (ref "IC9") (pin "29") (pinfunction "RA0/CVREF/AN0/ULPWU_29") (pintype "bidirectional"))
    )
    (net (code "12") (name "AD_VOUT_NREGV") (class "Default")
      (node (ref "IC8") (pin "6") (pinfunction "-IN_6") (pintype "input"))
      (node (ref "IC8") (pin "7") (pinfunction "OUT_7") (pintype "output"))
      (node (ref "IC9") (pin "38") (pinfunction "RE1/AN6/C1OUT/~{WR}_38") (pintype "bidirectional"))
    )
    (net (code "13") (name "AUX1") (class "Default")
      (node (ref "BACKUP") (pin "24") (pinfunction "24_24") (pintype "passive"))
      (node (ref "IC9") (pin "13") (pinfunction "RB0/AN10/FLT0/INT0_13") (pintype "bidirectional"))
    )
    (net (code "14") (name "BOT1") (class "Default")
      (node (ref "DEBUG") (pin "2") (pinfunction "2_2") (pintype "passive"))
      (node (ref "IC9") (pin "54") (pinfunction "RD0/C1INA/PSP0_54") (pintype "bidirectional"))
      (node (ref "R51") (pin "1") (pinfunction "1_1") (pintype "passive"))
    )
    (net (code "15") (name "BOT2") (class "Default")
      (node (ref "DEBUG") (pin "4") (pinfunction "4_4") (pintype "passive"))
      (node (ref "IC9") (pin "55") (pinfunction "RD1/C1INB/PSP1_55") (pintype "bidirectional"))
      (node (ref "R52") (pin "1") (pinfunction "1_1") (pintype "passive"))
    )
    (net (code "16") (name "BOT3") (class "Default")
      (node (ref "DEBUG") (pin "6") (pinfunction "6_6") (pintype "passive"))
      (node (ref "IC9") (pin "58") (pinfunction "RD2/C2INA/PSP2_58") (pintype "bidirectional"))
      (node (ref "R56") (pin "1") (pinfunction "1_1") (pintype "passive"))
    )
    (net (code "17") (name "CANRX") (class "Default")
      (node (ref "IC11") (pin "4") (pinfunction "RXD_4") (pintype "bidirectional"))
      (node (ref "IC9") (pin "16") (pinfunction "RB3/CANRX/CTED2/INT3_16") (pintype "bidirectional"))
    )
    (net (code "18") (name "CANTX") (class "Default")
      (node (ref "IC11") (pin "1") (pinfunction "TXD_1") (pintype "bidirectional"))
      (node (ref "IC9") (pin "15") (pinfunction "RB2/CANTX/CTED1/INT2_15") (pintype "bidirectional"))
    )
    (net (code "19") (name "CTL_3V3") (class "Default")
      (node (ref "IC3") (pin "3") (pinfunction "CTL_3") (pintype "passive"))
      (node (ref "IC9") (pin "18") (pinfunction "RG4/T0CKI_18") (pintype "bidirectional"))
      (node (ref "TP24") (pin "1") (pinfunction "P$1_1") (pintype "bidirectional"))
    )
    (net (code "20") (name "CTL_5V") (class "Default")
      (node (ref "IC2") (pin "3") (pinfunction "CTL_3") (pintype "passive"))
      (node (ref "IC9") (pin "19") (pinfunction "RF1_19") (pintype "bidirectional"))
      (node (ref "TP19") (pin "1") (pinfunction "P$1_1") (pintype "bidirectional"))
    )
    (net (code "21") (name "CTL_12V") (class "Default")
      (node (ref "IC1") (pin "3") (pinfunction "CTL_3") (pintype "passive"))
      (node (ref "IC9") (pin "20") (pinfunction "RB4/AN9/CTPLS/KBI0_20") (pintype "input"))
      (node (ref "TP16") (pin "1") (pinfunction "P$1_1") (pintype "bidirectional"))
    )
    (net (code "22") (name "CTL_NREGV") (class "Default")
      (node (ref "IC4") (pin "3") (pinfunction "CTL_3") (pintype "passive"))
      (node (ref "IC9") (pin "17") (pinfunction "RF0/MDMIN_17") (pintype "bidirectional"))
      (node (ref "TP32") (pin "1") (pinfunction "P$1_1") (pintype "bidirectional"))
    )
    (net (code "23") (name "GND") (class "Default")
      (node (ref "BACKUP") (pin "17") (pinfunction "17_17") (pintype "passive"))
      (node (ref "BACKUP") (pin "18") (pinfunction "18_18") (pintype "passive"))
      (node (ref "BACKUP") (pin "19") (pinfunction "19_19") (pintype "passive"))
      (node (ref "BACKUP") (pin "20") (pinfunction "20_20") (pintype "passive"))
      (node (ref "C1") (pin "2") (pinfunction "2_2") (pintype "passive"))
      (node (ref "C10") (pin "-") (pinfunction "-_-") (pintype "passive"))
      (node (ref "C11") (pin "-") (pinfunction "-_-") (pintype "passive"))
      (node (ref "C12") (pin "-") (pinfunction "-_-") (pintype "passive"))
      (node (ref "C13") (pin "1") (pinfunction "1_1") (pintype "passive"))
      (node (ref "C14") (pin "1") (pinfunction "1_1") (pintype "passive"))
      (node (ref "C15") (pin "1") (pinfunction "1_1") (pintype "passive"))
      (node (ref "C16") (pin "1") (pinfunction "1_1") (pintype "passive"))
      (node (ref "C17") (pin "1") (pinfunction "1_1") (pintype "passive"))
      (node (ref "C18") (pin "1") (pinfunction "1_1") (pintype "passive"))
      (node (ref "C19") (pin "1") (pinfunction "1_1") (pintype "passive"))
      (node (ref "C2") (pin "2") (pinfunction "2_2") (pintype "passive"))
      (node (ref "C20") (pin "1") (pinfunction "1_1") (pintype "passive"))
      (node (ref "C25") (pin "1") (pinfunction "1_1") (pintype "passive"))
      (node (ref "C26") (pin "1") (pinfunction "1_1") (pintype "passive"))
      (node (ref "C29") (pin "-") (pinfunction "-_-") (pintype "passive"))
      (node (ref "C30") (pin "-") (pinfunction "-_-") (pintype "passive"))
      (node (ref "C31") (pin "2") (pinfunction "2_2") (pintype "passive"))
      (node (ref "C32") (pin "2") (pinfunction "2_2") (pintype "passive"))
      (node (ref "C33") (pin "1") (pinfunction "1_1") (pintype "passive"))
      (node (ref "C34") (pin "1") (pinfunction "1_1") (pintype "passive"))
      (node (ref "C35") (pin "1") (pinfunction "1_1") (pintype "passive"))
      (node (ref "C36") (pin "1") (pinfunction "1_1") (pintype "passive"))
      (node (ref "C37") (pin "1") (pinfunction "1_1") (pintype "passive"))
      (node (ref "C38") (pin "1") (pinfunction "1_1") (pintype "passive"))
      (node (ref "C39") (pin "2") (pinfunction "2_2") (pintype "passive"))
      (node (ref "C4") (pin "2") (pinfunction "2_2") (pintype "passive"))
      (node (ref "C5") (pin "-") (pinfunction "-_-") (pintype "passive"))
      (node (ref "C56") (pin "-") (pinfunction "-_-") (pintype "passive"))
      (node (ref "C57") (pin "-") (pinfunction "-_-") (pintype "passive"))
      (node (ref "C58") (pin "2") (pinfunction "2_2") (pintype "passive"))
      (node (ref "C59") (pin "1") (pinfunction "1_1") (pintype "passive"))
      (node (ref "C60") (pin "1") (pinfunction "1_1") (pintype "passive"))
      (node (ref "C61") (pin "1") (pinfunction "1_1") (pintype "passive"))
      (node (ref "C62") (pin "1") (pinfunction "1_1") (pintype "passive"))
      (node (ref "C65") (pin "2") (pinfunction "2_2") (pintype "passive"))
      (node (ref "C66") (pin "2") (pinfunction "2_2") (pintype "passive"))
      (node (ref "C67") (pin "2") (pinfunction "2_2") (pintype "passive"))
      (node (ref "C68") (pin "2") (pinfunction "2_2") (pintype "passive"))
      (node (ref "C69") (pin "2") (pinfunction "2_2") (pintype "passive"))
      (node (ref "C7") (pin "-") (pinfunction "-_-") (pintype "passive"))
      (node (ref "C70") (pin "1") (pinfunction "1_1") (pintype "passive"))
      (node (ref "C71") (pin "1") (pinfunction "1_1") (pintype "passive"))
      (node (ref "C9") (pin "-") (pinfunction "-_-") (pintype "passive"))
      (node (ref "CAN") (pin "4") (pinfunction "4_4") (pintype "bidirectional"))
      (node (ref "DEBUG") (pin "1") (pinfunction "1_1") (pintype "passive"))
      (node (ref "DEBUG") (pin "3") (pinfunction "3_3") (pintype "passive"))
      (node (ref "DEBUG") (pin "5") (pinfunction "5_5") (pintype "passive"))
      (node (ref "IC1") (pin "2") (pinfunction "GND_2") (pintype "power_in"))
      (node (ref "IC11") (pin "2") (pinfunction "VSS_2") (pintype "power_in"))
      (node (ref "IC2") (pin "2") (pinfunction "GND_2") (pintype "power_in"))
      (node (ref "IC3") (pin "2") (pinfunction "GND_2") (pintype "power_in"))
      (node (ref "IC4") (pin "2") (pinfunction "GND_2") (pintype "power_in"))
      (node (ref "IC4") (pin "6") (pinfunction "SENSE_6") (pintype "passive"))
      (node (ref "IC5") (pin "4") (pinfunction "V-_4") (pintype "power_in"))
      (node (ref "IC6") (pin "4") (pinfunction "V-_4") (pintype "power_in"))
      (node (ref "IC7") (pin "4") (pinfunction "V-_4") (pintype "power_in"))
      (node (ref "IC8") (pin "4") (pinfunction "V-_4") (pintype "power_in"))
      (node (ref "IC9") (pin "26") (pinfunction "VSS_26") (pintype "power_in"))
      (node (ref "IC9") (pin "42") (pinfunction "AVSS_42") (pintype "power_in"))
      (node (ref "IC9") (pin "43") (pinfunction "VSS_43") (pintype "power_in"))
      (node (ref "IC9") (pin "56") (pinfunction "VSS_56") (pintype "power_in"))
      (node (ref "IC9") (pin "8") (pinfunction "VSS_8") (pintype "power_in"))
      (node (ref "ICSP") (pin "3") (pinfunction "GND_3") (pintype "passive"))
      (node (ref "LED10") (pin "C") (pinfunction "C_C") (pintype "passive"))
      (node (ref "LED11") (pin "C") (pinfunction "C_C") (pintype "passive"))
      (node (ref "LED12") (pin "C") (pinfunction "C_C") (pintype "passive"))
      (node (ref "LED13") (pin "C") (pinfunction "C_C") (pintype "passive"))
      (node (ref "LED14") (pin "C") (pinfunction "C_C") (pintype "passive"))
      (node (ref "LED15") (pin "C") (pinfunction "C_C") (pintype "passive"))
      (node (ref "LED4") (pin "C") (pinfunction "C_C") (pintype "passive"))
      (node (ref "LED5") (pin "C") (pinfunction "C_C") (pintype "passive"))
      (node (ref "LED6") (pin "C") (pinfunction "C_C") (pintype "passive"))
      (node (ref "LED7") (pin "C") (pinfunction "C_C") (pintype "passive"))
      (node (ref "LED8") (pin "C") (pinfunction "C_C") (pintype "passive"))
      (node (ref "LED9") (pin "C") (pinfunction "C_C") (pintype "passive"))
      (node (ref "R1") (pin "1") (pinfunction "1_1") (pintype "passive"))
      (node (ref "R10") (pin "1") (pinfunction "1_1") (pintype "passive"))
      (node (ref "R11") (pin "1") (pinfunction "1_1") (pintype "passive"))
      (node (ref "R14") (pin "1") (pinfunction "1_1") (pintype "passive"))
      (node (ref "R2") (pin "1") (pinfunction "1_1") (pintype "passive"))
      (node (ref "R26") (pin "2") (pinfunction "2_2") (pintype "passive"))
      (node (ref "R31") (pin "2") (pinfunction "2_2") (pintype "passive"))
      (node (ref "R37") (pin "2") (pinfunction "2_2") (pintype "passive"))
      (node (ref "R4") (pin "1") (pinfunction "1_1") (pintype "passive"))
      (node (ref "R43") (pin "2") (pinfunction "2_2") (pintype "passive"))
      (node (ref "R46") (pin "2") (pinfunction "2_2") (pintype "passive"))
      (node (ref "R5") (pin "1") (pinfunction "1_1") (pintype "passive"))
      (node (ref "R58") (pin "1") (pinfunction "1_1") (pintype "passive"))
      (node (ref "R63") (pin "1") (pinfunction "1_1") (pintype "passive"))
      (node (ref "R71") (pin "2") (pinfunction "2_2") (pintype "passive"))
      (node (ref "R73") (pin "1") (pinfunction "1_1") (pintype "passive"))
      (node (ref "R77") (pin "2") (pinfunction "2_2") (pintype "passive"))
      (node (ref "R8") (pin "1") (pinfunction "1_1") (pintype "passive"))
      (node (ref "SERIAL") (pin "4") (pinfunction "4_4") (pintype "bidirectional"))
      (node (ref "U1") (pin "1") (pinfunction "GND_1") (pintype "power_in"))
      (node (ref "U2") (pin "1") (pinfunction "GND_1") (pintype "power_in"))
      (node (ref "U4") (pin "1") (pinfunction "GND_1") (pintype "power_in"))
      (node (ref "U6") (pin "4") (pinfunction "AGND_4") (pintype "passive"))
      (node (ref "U6") (pin "5") (pinfunction "PGND_5") (pintype "passive"))
      (node (ref "V_BUS") (pin "10") (pinfunction "10_10") (pintype "passive"))
      (node (ref "V_BUS") (pin "12") (pinfunction "12_12") (pintype "passive"))
      (node (ref "V_BUS") (pin "14") (pinfunction "14_14") (pintype "passive"))
      (node (ref "V_BUS") (pin "16") (pinfunction "16_16") (pintype "passive"))
      (node (ref "V_BUS") (pin "18") (pinfunction "18_18") (pintype "passive"))
      (node (ref "V_BUS") (pin "2") (pinfunction "2_2") (pintype "passive"))
      (node (ref "V_BUS") (pin "20") (pinfunction "20_20") (pintype "passive"))
      (node (ref "V_BUS") (pin "22") (pinfunction "22_22") (pintype "passive"))
      (node (ref "V_BUS") (pin "24") (pinfunction "24_24") (pintype "passive"))
      (node (ref "V_BUS") (pin "26") (pinfunction "26_26") (pintype "passive"))
      (node (ref "V_BUS") (pin "28") (pinfunction "28_28") (pintype "passive"))
      (node (ref "V_BUS") (pin "30") (pinfunction "30_30") (pintype "passive"))
      (node (ref "V_BUS") (pin "32") (pinfunction "32_32") (pintype "passive"))
      (node (ref "V_BUS") (pin "34") (pinfunction "34_34") (pintype "passive"))
      (node (ref "V_BUS") (pin "36") (pinfunction "36_36") (pintype "passive"))
      (node (ref "V_BUS") (pin "38") (pinfunction "38_38") (pintype "passive"))
      (node (ref "V_BUS") (pin "4") (pinfunction "4_4") (pintype "passive"))
      (node (ref "V_BUS") (pin "40") (pinfunction "40_40") (pintype "passive"))
      (node (ref "V_BUS") (pin "6") (pinfunction "6_6") (pintype "passive"))
      (node (ref "V_BUS") (pin "8") (pinfunction "8_8") (pintype "passive"))
    )
    (net (code "24") (name "LED1") (class "Default")
      (node (ref "IC9") (pin "49") (pinfunction "RC1/SOSCI_49") (pintype "bidirectional"))
      (node (ref "LED3") (pin "C") (pinfunction "C_C") (pintype "passive"))
    )
    (net (code "25") (name "LED2") (class "Default")
      (node (ref "IC9") (pin "50") (pinfunction "RC2/T1G/CCP2_50") (pintype "bidirectional"))
      (node (ref "LED2") (pin "C") (pinfunction "C_C") (pintype "passive"))
    )
    (net (code "26") (name "LED3") (class "Default")
      (node (ref "IC9") (pin "51") (pinfunction "RC3/REFO/SCL/SCK_51") (pintype "bidirectional"))
      (node (ref "LED1") (pin "C") (pinfunction "C_C") (pintype "passive"))
    )
    (net (code "27") (name "Net-(C3-Pad2)") (class "Default")
      (node (ref "C3") (pin "2") (pinfunction "2_2") (pintype "passive"))
      (node (ref "R1") (pin "2") (pinfunction "2_2") (pintype "passive"))
    )
    (net (code "28") (name "Net-(C4-Pad1)") (class "Default")
      (node (ref "C4") (pin "1") (pinfunction "1_1") (pintype "passive"))
      (node (ref "R3") (pin "1") (pinfunction "1_1") (pintype "passive"))
    )
    (net (code "29") (name "Net-(C25-Pad2)") (class "Default")
      (node (ref "C25") (pin "2") (pinfunction "2_2") (pintype "passive"))
      (node (ref "R47") (pin "1") (pinfunction "1_1") (pintype "passive"))
      (node (ref "R53") (pin "2") (pinfunction "2_2") (pintype "passive"))
    )
    (net (code "30") (name "Net-(IC1-GATE)") (class "Default")
      (node (ref "IC1") (pin "5") (pinfunction "GATE_5") (pintype "passive"))
      (node (ref "R13") (pin "2") (pinfunction "2_2") (pintype "passive"))
      (node (ref "T1") (pin "2") (pinfunction "G_2") (pintype "passive"))
      (node (ref "T2") (pin "4") (pinfunction "G_4") (pintype "passive"))
    )
    (net (code "31") (name "Net-(IC1-STAT)") (class "Default")
      (node (ref "IC1") (pin "4") (pinfunction "STAT_4") (pintype "passive"))
      (node (ref "R12") (pin "2") (pinfunction "2_2") (pintype "passive"))
      (node (ref "T1") (pin "4") (pinfunction "G_4") (pintype "passive"))
      (node (ref "T2") (pin "2") (pinfunction "G_2") (pintype "passive"))
    )
    (net (code "32") (name "Net-(IC2-GATE)") (class "Default")
      (node (ref "IC2") (pin "5") (pinfunction "GATE_5") (pintype "passive"))
      (node (ref "R16") (pin "2") (pinfunction "2_2") (pintype "passive"))
      (node (ref "T3") (pin "2") (pinfunction "G_2") (pintype "passive"))
      (node (ref "T4") (pin "4") (pinfunction "G_4") (pintype "passive"))
    )
    (net (code "33") (name "Net-(IC2-STAT)") (class "Default")
      (node (ref "IC2") (pin "4") (pinfunction "STAT_4") (pintype "passive"))
      (node (ref "R30") (pin "2") (pinfunction "2_2") (pintype "passive"))
      (node (ref "T3") (pin "4") (pinfunction "G_4") (pintype "passive"))
      (node (ref "T4") (pin "2") (pinfunction "G_2") (pintype "passive"))
    )
    (net (code "34") (name "Net-(IC3-GATE)") (class "Default")
      (node (ref "IC3") (pin "5") (pinfunction "GATE_5") (pintype "passive"))
      (node (ref "R19") (pin "2") (pinfunction "2_2") (pintype "passive"))
      (node (ref "T5") (pin "2") (pinfunction "G_2") (pintype "passive"))
      (node (ref "T6") (pin "4") (pinfunction "G_4") (pintype "passive"))
    )
    (net (code "35") (name "Net-(IC3-STAT)") (class "Default")
      (node (ref "IC3") (pin "4") (pinfunction "STAT_4") (pintype "passive"))
      (node (ref "R76") (pin "2") (pinfunction "2_2") (pintype "passive"))
      (node (ref "T5") (pin "4") (pinfunction "G_4") (pintype "passive"))
      (node (ref "T6") (pin "2") (pinfunction "G_2") (pintype "passive"))
    )
    (net (code "36") (name "Net-(IC4-GATE)") (class "Default")
      (node (ref "IC4") (pin "5") (pinfunction "GATE_5") (pintype "passive"))
      (node (ref "Q2") (pin "1") (pinfunction "G_1") (pintype "passive"))
    )
    (net (code "37") (name "Net-(IC5A-+IN)") (class "Default")
      (node (ref "IC5") (pin "3") (pinfunction "+IN_3") (pintype "input"))
      (node (ref "R21") (pin "1") (pinfunction "1_1") (pintype "passive"))
      (node (ref "R26") (pin "1") (pinfunction "1_1") (pintype "passive"))
    )
    (net (code "38") (name "Net-(IC5A--IN)") (class "Default")
      (node (ref "IC5") (pin "2") (pinfunction "-IN_2") (pintype "input"))
      (node (ref "R28") (pin "1") (pinfunction "1_1") (pintype "passive"))
      (node (ref "R29") (pin "2") (pinfunction "2_2") (pintype "passive"))
    )
    (net (code "39") (name "Net-(IC5B-+IN)") (class "Default")
      (node (ref "IC5") (pin "5") (pinfunction "+IN_5") (pintype "input"))
      (node (ref "R20") (pin "2") (pinfunction "2_2") (pintype "passive"))
      (node (ref "R31") (pin "1") (pinfunction "1_1") (pintype "passive"))
    )
    (net (code "40") (name "Net-(IC6A-+IN)") (class "Default")
      (node (ref "IC6") (pin "3") (pinfunction "+IN_3") (pintype "input"))
      (node (ref "R33") (pin "1") (pinfunction "1_1") (pintype "passive"))
      (node (ref "R71") (pin "1") (pinfunction "1_1") (pintype "passive"))
    )
    (net (code "41") (name "Net-(IC6A--IN)") (class "Default")
      (node (ref "IC6") (pin "2") (pinfunction "-IN_2") (pintype "input"))
      (node (ref "R34") (pin "1") (pinfunction "1_1") (pintype "passive"))
      (node (ref "R35") (pin "2") (pinfunction "2_2") (pintype "passive"))
    )
    (net (code "42") (name "Net-(IC6B-+IN)") (class "Default")
      (node (ref "IC6") (pin "5") (pinfunction "+IN_5") (pintype "input"))
      (node (ref "R75") (pin "2") (pinfunction "2_2") (pintype "passive"))
    )
    (net (code "43") (name "Net-(IC6B--IN)") (class "Default")
      (node (ref "IC6") (pin "6") (pinfunction "-IN_6") (pintype "input"))
      (node (ref "R72") (pin "1") (pinfunction "1_1") (pintype "passive"))
      (node (ref "R73") (pin "2") (pinfunction "2_2") (pintype "passive"))
    )
    (net (code "44") (name "Net-(IC7A-+IN)") (class "Default")
      (node (ref "IC7") (pin "3") (pinfunction "+IN_3") (pintype "input"))
      (node (ref "R11") (pin "2") (pinfunction "2_2") (pintype "passive"))
      (node (ref "R22") (pin "1") (pinfunction "1_1") (pintype "passive"))
    )
    (net (code "45") (name "Net-(IC7A--IN)") (class "Default")
      (node (ref "IC7") (pin "2") (pinfunction "-IN_2") (pintype "input"))
      (node (ref "R23") (pin "1") (pinfunction "1_1") (pintype "passive"))
      (node (ref "R24") (pin "2") (pinfunction "2_2") (pintype "passive"))
    )
    (net (code "46") (name "Net-(IC7B-+IN)") (class "Default")
      (node (ref "IC7") (pin "5") (pinfunction "+IN_5") (pintype "input"))
      (node (ref "R25") (pin "2") (pinfunction "2_2") (pintype "passive"))
      (node (ref "R46") (pin "1") (pinfunction "1_1") (pintype "passive"))
    )
    (net (code "47") (name "Net-(IC8A-+IN)") (class "Default")
      (node (ref "IC8") (pin "3") (pinfunction "+IN_3") (pintype "input"))
      (node (ref "R39") (pin "1") (pinfunction "1_1") (pintype "passive"))
      (node (ref "R77") (pin "1") (pinfunction "1_1") (pintype "passive"))
    )
    (net (code "48") (name "Net-(IC8A--IN)") (class "Default")
      (node (ref "IC8") (pin "2") (pinfunction "-IN_2") (pintype "input"))
      (node (ref "R40") (pin "1") (pinfunction "1_1") (pintype "passive"))
      (node (ref "R41") (pin "2") (pinfunction "2_2") (pintype "passive"))
    )
    (net (code "49") (name "Net-(IC8B-+IN)") (class "Default")
      (node (ref "IC8") (pin "5") (pinfunction "+IN_5") (pintype "input"))
      (node (ref "R42") (pin "2") (pinfunction "2_2") (pintype "passive"))
      (node (ref "R43") (pin "1") (pinfunction "1_1") (pintype "passive"))
    )
    (net (code "50") (name "Net-(IC9-VDDCORE{slash}VCAP)") (class "Default")
      (node (ref "C26") (pin "2") (pinfunction "2_2") (pintype "passive"))
      (node (ref "IC9") (pin "33") (pinfunction "VDDCORE/VCAP_33") (pintype "bidirectional"))
    )
    (net (code "51") (name "Net-(IC11-CANH)") (class "Default")
      (node (ref "CAN") (pin "2") (pinfunction "2_2") (pintype "bidirectional"))
      (node (ref "IC11") (pin "7") (pinfunction "CANH_7") (pintype "input"))
      (node (ref "R64") (pin "2") (pinfunction "2_2") (pintype "passive"))
    )
    (net (code "52") (name "Net-(IC11-CANL)") (class "Default")
      (node (ref "CAN") (pin "3") (pinfunction "3_3") (pintype "bidirectional"))
      (node (ref "IC11") (pin "6") (pinfunction "CANL_6") (pintype "input"))
      (node (ref "JP2") (pin "1") (pinfunction "1_1") (pintype "passive"))
    )
    (net (code "53") (name "Net-(IC11-RS)") (class "Default")
      (node (ref "IC11") (pin "8") (pinfunction "RS_8") (pintype "input"))
      (node (ref "R63") (pin "2") (pinfunction "2_2") (pintype "passive"))
    )
    (net (code "54") (name "Net-(JP2-Pad2)") (class "Default")
      (node (ref "JP2") (pin "2") (pinfunction "2_2") (pintype "passive"))
      (node (ref "R64") (pin "1") (pinfunction "1_1") (pintype "passive"))
    )
    (net (code "55") (name "Net-(LED1-PadA)") (class "Default")
      (node (ref "LED1") (pin "A") (pinfunction "A_A") (pintype "passive"))
      (node (ref "R48") (pin "2") (pinfunction "2_2") (pintype "passive"))
    )
    (net (code "56") (name "Net-(LED2-PadA)") (class "Default")
      (node (ref "LED2") (pin "A") (pinfunction "A_A") (pintype "passive"))
      (node (ref "R49") (pin "2") (pinfunction "2_2") (pintype "passive"))
    )
    (net (code "57") (name "Net-(LED3-PadA)") (class "Default")
      (node (ref "LED3") (pin "A") (pinfunction "A_A") (pintype "passive"))
      (node (ref "R50") (pin "2") (pinfunction "2_2") (pintype "passive"))
    )
    (net (code "58") (name "Net-(LED4-PadA)") (class "Default")
      (node (ref "LED4") (pin "A") (pinfunction "A_A") (pintype "passive"))
      (node (ref "R15") (pin "2") (pinfunction "2_2") (pintype "passive"))
    )
    (net (code "59") (name "Net-(LED5-PadA)") (class "Default")
      (node (ref "LED5") (pin "A") (pinfunction "A_A") (pintype "passive"))
      (node (ref "R17") (pin "2") (pinfunction "2_2") (pintype "passive"))
    )
    (net (code "60") (name "Net-(LED6-PadA)") (class "Default")
      (node (ref "LED6") (pin "A") (pinfunction "A_A") (pintype "passive"))
      (node (ref "R18") (pin "2") (pinfunction "2_2") (pintype "passive"))
    )
    (net (code "61") (name "Net-(LED7-PadA)") (class "Default")
      (node (ref "LED7") (pin "A") (pinfunction "A_A") (pintype "passive"))
      (node (ref "R45") (pin "2") (pinfunction "2_2") (pintype "passive"))
    )
    (net (code "62") (name "Net-(LED8-PadA)") (class "Default")
      (node (ref "LED8") (pin "A") (pinfunction "A_A") (pintype "passive"))
      (node (ref "R54") (pin "2") (pinfunction "2_2") (pintype "passive"))
    )
    (net (code "63") (name "Net-(LED9-PadA)") (class "Default")
      (node (ref "LED9") (pin "A") (pinfunction "A_A") (pintype "passive"))
      (node (ref "R55") (pin "2") (pinfunction "2_2") (pintype "passive"))
    )
    (net (code "64") (name "Net-(LED10-PadA)") (class "Default")
      (node (ref "LED10") (pin "A") (pinfunction "A_A") (pintype "passive"))
      (node (ref "R59") (pin "2") (pinfunction "2_2") (pintype "passive"))
    )
    (net (code "65") (name "Net-(LED11-PadA)") (class "Default")
      (node (ref "LED11") (pin "A") (pinfunction "A_A") (pintype "passive"))
      (node (ref "R60") (pin "2") (pinfunction "2_2") (pintype "passive"))
    )
    (net (code "66") (name "Net-(LED12-PadA)") (class "Default")
      (node (ref "LED12") (pin "A") (pinfunction "A_A") (pintype "passive"))
      (node (ref "R61") (pin "2") (pinfunction "2_2") (pintype "passive"))
    )
    (net (code "67") (name "Net-(LED13-PadA)") (class "Default")
      (node (ref "LED13") (pin "A") (pinfunction "A_A") (pintype "passive"))
      (node (ref "R62") (pin "2") (pinfunction "2_2") (pintype "passive"))
    )
    (net (code "68") (name "Net-(LED14-PadA)") (class "Default")
      (node (ref "LED14") (pin "A") (pinfunction "A_A") (pintype "passive"))
      (node (ref "R65") (pin "2") (pinfunction "2_2") (pintype "passive"))
    )
    (net (code "69") (name "Net-(LED15-PadA)") (class "Default")
      (node (ref "LED15") (pin "A") (pinfunction "A_A") (pintype "passive"))
      (node (ref "R66") (pin "2") (pinfunction "2_2") (pintype "passive"))
    )
    (net (code "70") (name "Net-(Q1-DRAIN)") (class "Default")
      (node (ref "D6") (pin "A") (pinfunction "A_A") (pintype "passive"))
      (node (ref "L1") (pin "2") (pinfunction "2_2") (pintype "passive"))
      (node (ref "Q1") (pin "5") (pinfunction "DRAIN_5") (pintype "passive"))
    )
    (net (code "71") (name "Net-(Q1-GATE)") (class "Default")
      (node (ref "Q1") (pin "4") (pinfunction "GATE_4") (pintype "passive"))
      (node (ref "U6") (pin "6") (pinfunction "DR_6") (pintype "passive"))
    )
    (net (code "72") (name "Net-(Q1-SOURCE)") (class "Default")
      (node (ref "Q1") (pin "1") (pinfunction "SOURCE_1") (pintype "passive"))
      (node (ref "R4") (pin "2") (pinfunction "2_2") (pintype "passive"))
    )
    (net (code "73") (name "Net-(R36-Pad2)") (class "Default")
      (node (ref "R36") (pin "2") (pinfunction "2_2") (pintype "passive"))
      (node (ref "R37") (pin "1") (pinfunction "1_1") (pintype "passive"))
      (node (ref "R74") (pin "1") (pinfunction "1_1") (pintype "passive"))
    )
    (net (code "74") (name "Net-(R74-Pad2)") (class "Default")
      (node (ref "R74") (pin "2") (pinfunction "2_2") (pintype "passive"))
      (node (ref "R75") (pin "1") (pinfunction "1_1") (pintype "passive"))
    )
    (net (code "75") (name "Net-(T1A-S)") (class "Default")
      (node (ref "R13") (pin "1") (pinfunction "1_1") (pintype "passive"))
      (node (ref "T1") (pin "1") (pinfunction "S_1") (pintype "passive"))
      (node (ref "T2") (pin "3") (pinfunction "S_3") (pintype "passive"))
    )
    (net (code "76") (name "Net-(T1B-S)") (class "Default")
      (node (ref "R12") (pin "1") (pinfunction "1_1") (pintype "passive"))
      (node (ref "T1") (pin "3") (pinfunction "S_3") (pintype "passive"))
      (node (ref "T2") (pin "1") (pinfunction "S_1") (pintype "passive"))
    )
    (net (code "77") (name "Net-(T3A-S)") (class "Default")
      (node (ref "R16") (pin "1") (pinfunction "1_1") (pintype "passive"))
      (node (ref "T3") (pin "1") (pinfunction "S_1") (pintype "passive"))
      (node (ref "T4") (pin "3") (pinfunction "S_3") (pintype "passive"))
    )
    (net (code "78") (name "Net-(T3B-S)") (class "Default")
      (node (ref "R30") (pin "1") (pinfunction "1_1") (pintype "passive"))
      (node (ref "T3") (pin "3") (pinfunction "S_3") (pintype "passive"))
      (node (ref "T4") (pin "1") (pinfunction "S_1") (pintype "passive"))
    )
    (net (code "79") (name "Net-(T5A-S)") (class "Default")
      (node (ref "R19") (pin "1") (pinfunction "1_1") (pintype "passive"))
      (node (ref "T5") (pin "1") (pinfunction "S_1") (pintype "passive"))
      (node (ref "T6") (pin "3") (pinfunction "S_3") (pintype "passive"))
    )
    (net (code "80") (name "Net-(T5B-S)") (class "Default")
      (node (ref "R76") (pin "1") (pinfunction "1_1") (pintype "passive"))
      (node (ref "T5") (pin "3") (pinfunction "S_3") (pintype "passive"))
      (node (ref "T6") (pin "1") (pinfunction "S_1") (pintype "passive"))
    )
    (net (code "81") (name "Net-(U1-EN)") (class "Default")
      (node (ref "SJ3") (pin "1") (pinfunction "1_1") (pintype "passive"))
      (node (ref "U1") (pin "5") (pinfunction "EN_5") (pintype "input"))
    )
    (net (code "82") (name "Net-(U1-SW)") (class "Default")
      (node (ref "C6") (pin "2") (pinfunction "2_2") (pintype "passive"))
      (node (ref "L3") (pin "1") (pinfunction "1_1") (pintype "passive"))
      (node (ref "U1") (pin "2") (pinfunction "SW_2") (pintype "power_in"))
    )
    (net (code "83") (name "Net-(U1-VBST)") (class "Default")
      (node (ref "C6") (pin "1") (pinfunction "1_1") (pintype "passive"))
      (node (ref "U1") (pin "6") (pinfunction "VBST_6") (pintype "power_in"))
    )
    (net (code "84") (name "Net-(U1-VFB)") (class "Default")
      (node (ref "R7") (pin "1") (pinfunction "1_1") (pintype "passive"))
      (node (ref "R8") (pin "2") (pinfunction "2_2") (pintype "passive"))
      (node (ref "U1") (pin "4") (pinfunction "VFB_4") (pintype "input"))
    )
    (net (code "85") (name "Net-(U2-EN)") (class "Default")
      (node (ref "SJ4") (pin "1") (pinfunction "1_1") (pintype "passive"))
      (node (ref "U2") (pin "5") (pinfunction "EN_5") (pintype "input"))
    )
    (net (code "86") (name "Net-(U2-SW)") (class "Default")
      (node (ref "C8") (pin "2") (pinfunction "2_2") (pintype "passive"))
      (node (ref "L2") (pin "1") (pinfunction "1_1") (pintype "passive"))
      (node (ref "U2") (pin "2") (pinfunction "SW_2") (pintype "power_in"))
    )
    (net (code "87") (name "Net-(U2-VBST)") (class "Default")
      (node (ref "C8") (pin "1") (pinfunction "1_1") (pintype "passive"))
      (node (ref "U2") (pin "6") (pinfunction "VBST_6") (pintype "power_in"))
    )
    (net (code "88") (name "Net-(U2-VFB)") (class "Default")
      (node (ref "R10") (pin "2") (pinfunction "2_2") (pintype "passive"))
      (node (ref "R9") (pin "1") (pinfunction "1_1") (pintype "passive"))
      (node (ref "U2") (pin "4") (pinfunction "VFB_4") (pintype "input"))
    )
    (net (code "89") (name "Net-(U4-EN)") (class "Default")
      (node (ref "SJ5") (pin "1") (pinfunction "1_1") (pintype "passive"))
      (node (ref "U4") (pin "5") (pinfunction "EN_5") (pintype "input"))
    )
    (net (code "90") (name "Net-(U4-SW)") (class "Default")
      (node (ref "C28") (pin "2") (pinfunction "2_2") (pintype "passive"))
      (node (ref "L4") (pin "1") (pinfunction "1_1") (pintype "passive"))
      (node (ref "U4") (pin "2") (pinfunction "SW_2") (pintype "power_in"))
    )
    (net (code "91") (name "Net-(U4-VBST)") (class "Default")
      (node (ref "C28") (pin "1") (pinfunction "1_1") (pintype "passive"))
      (node (ref "U4") (pin "6") (pinfunction "VBST_6") (pintype "power_in"))
    )
    (net (code "92") (name "Net-(U4-VFB)") (class "Default")
      (node (ref "R57") (pin "1") (pinfunction "1_1") (pintype "passive"))
      (node (ref "R58") (pin "2") (pinfunction "2_2") (pintype "passive"))
      (node (ref "U4") (pin "4") (pinfunction "VFB_4") (pintype "input"))
    )
    (net (code "93") (name "Net-(U6-COMP)") (class "Default")
      (node (ref "C2") (pin "1") (pinfunction "1_1") (pintype "passive"))
      (node (ref "C3") (pin "1") (pinfunction "1_1") (pintype "passive"))
      (node (ref "U6") (pin "2") (pinfunction "COMP_2") (pintype "passive"))
    )
    (net (code "94") (name "Net-(U6-FA{slash}SYNC{slash}SD)") (class "Default")
      (node (ref "R2") (pin "2") (pinfunction "2_2") (pintype "passive"))
      (node (ref "U6") (pin "7") (pinfunction "FA/SYNC/SD_7") (pintype "passive"))
    )
    (net (code "95") (name "Net-(U6-FB)") (class "Default")
      (node (ref "R5") (pin "2") (pinfunction "2_2") (pintype "passive"))
      (node (ref "R6") (pin "2") (pinfunction "2_2") (pintype "passive"))
      (node (ref "U6") (pin "3") (pinfunction "FB_3") (pintype "passive"))
    )
    (net (code "96") (name "Net-(U6-ISEN)") (class "Default")
      (node (ref "R3") (pin "2") (pinfunction "2_2") (pintype "passive"))
      (node (ref "U6") (pin "1") (pinfunction "ISEN_1") (pintype "passive"))
    )
    (net (code "97") (name "OSC1") (class "Default")
      (node (ref "C70") (pin "2") (pinfunction "2_2") (pintype "passive"))
      (node (ref "IC9") (pin "46") (pinfunction "OSC1/CLKIN/RA7_46") (pintype "bidirectional"))
      (node (ref "Q3") (pin "1") (pinfunction "1_1") (pintype "passive"))
    )
    (net (code "98") (name "OSC2") (class "Default")
      (node (ref "C71") (pin "2") (pinfunction "2_2") (pintype "passive"))
      (node (ref "IC9") (pin "47") (pinfunction "OSC2/CLKOUT/RA6_47") (pintype "bidirectional"))
      (node (ref "Q3") (pin "2") (pinfunction "2_2") (pintype "passive"))
    )
    (net (code "99") (name "PGC") (class "Default")
      (node (ref "IC9") (pin "22") (pinfunction "RB6/PGC/KBI2_22") (pintype "bidirectional"))
      (node (ref "ICSP") (pin "5") (pinfunction "PGC_5") (pintype "passive"))
    )
    (net (code "100") (name "PGD") (class "Default")
      (node (ref "IC9") (pin "23") (pinfunction "RB7/PGD/T3G/KBI3_23") (pintype "bidirectional"))
      (node (ref "ICSP") (pin "4") (pinfunction "PGD_4") (pintype "passive"))
    )
    (net (code "101") (name "RX") (class "Default")
      (node (ref "IC9") (pin "6") (pinfunction "RG0/RX1/DT1_6") (pintype "bidirectional"))
      (node (ref "SERIAL") (pin "3") (pinfunction "3_3") (pintype "bidirectional"))
    )
    (net (code "102") (name "STAT1") (class "Default")
      (node (ref "BACKUP") (pin "22") (pinfunction "22_22") (pintype "passive"))
      (node (ref "IC9") (pin "2") (pinfunction "RD4/ECCP1/P1A/PSP4_2") (pintype "bidirectional"))
    )
    (net (code "103") (name "STAT2") (class "Default")
      (node (ref "BACKUP") (pin "21") (pinfunction "21_21") (pintype "passive"))
      (node (ref "IC9") (pin "1") (pinfunction "RC7/CCP4_1") (pintype "bidirectional"))
    )
    (net (code "104") (name "TX") (class "Default")
      (node (ref "IC9") (pin "12") (pinfunction "RG3/TX1/CK1_12") (pintype "bidirectional"))
      (node (ref "SERIAL") (pin "2") (pinfunction "2_2") (pintype "bidirectional"))
    )
    (net (code "105") (name "VBAT") (class "Default")
      (node (ref "BACKUP") (pin "13") (pinfunction "13_13") (pintype "passive"))
      (node (ref "BACKUP") (pin "14") (pinfunction "14_14") (pintype "passive"))
      (node (ref "BACKUP") (pin "15") (pinfunction "15_15") (pintype "passive"))
      (node (ref "BACKUP") (pin "16") (pinfunction "16_16") (pintype "passive"))
      (node (ref "C1") (pin "1") (pinfunction "1_1") (pintype "passive"))
      (node (ref "C11") (pin "+") (pinfunction "+_+") (pintype "passive"))
      (node (ref "C19") (pin "2") (pinfunction "2_2") (pintype "passive"))
      (node (ref "C29") (pin "+") (pinfunction "+_+") (pintype "passive"))
      (node (ref "C5") (pin "+") (pinfunction "+_+") (pintype "passive"))
      (node (ref "C60") (pin "2") (pinfunction "2_2") (pintype "passive"))
      (node (ref "C62") (pin "2") (pinfunction "2_2") (pintype "passive"))
      (node (ref "C66") (pin "1") (pinfunction "1_1") (pintype "passive"))
      (node (ref "C9") (pin "+") (pinfunction "+_+") (pintype "passive"))
      (node (ref "IC4") (pin "1") (pinfunction "VIN_1") (pintype "power_in"))
      (node (ref "L1") (pin "1") (pinfunction "1_1") (pintype "passive"))
      (node (ref "Q2") (pin "2") (pinfunction "S_2") (pintype "passive"))
      (node (ref "R66") (pin "1") (pinfunction "1_1") (pintype "passive"))
      (node (ref "SJ3") (pin "2") (pinfunction "2_2") (pintype "passive"))
      (node (ref "SJ4") (pin "2") (pinfunction "2_2") (pintype "passive"))
      (node (ref "SJ5") (pin "2") (pinfunction "2_2") (pintype "passive"))
      (node (ref "U1") (pin "3") (pinfunction "VIN_3") (pintype "power_in"))
      (node (ref "U2") (pin "3") (pinfunction "VIN_3") (pintype "power_in"))
      (node (ref "U4") (pin "3") (pinfunction "VIN_3") (pintype "power_in"))
      (node (ref "U6") (pin "8") (pinfunction "VIN_8") (pintype "passive"))
    )
    (net (code "106") (name "VCC") (class "Default")
      (node (ref "BACKUP") (pin "25") (pinfunction "25_25") (pintype "passive"))
      (node (ref "BACKUP") (pin "26") (pinfunction "26_26") (pintype "passive"))
      (node (ref "C30") (pin "+") (pinfunction "+_+") (pintype "passive"))
      (node (ref "C31") (pin "1") (pinfunction "1_1") (pintype "passive"))
      (node (ref "C32") (pin "1") (pinfunction "1_1") (pintype "passive"))
      (node (ref "C33") (pin "2") (pinfunction "2_2") (pintype "passive"))
      (node (ref "C34") (pin "2") (pinfunction "2_2") (pintype "passive"))
      (node (ref "C35") (pin "2") (pinfunction "2_2") (pintype "passive"))
      (node (ref "C36") (pin "2") (pinfunction "2_2") (pintype "passive"))
      (node (ref "C37") (pin "2") (pinfunction "2_2") (pintype "passive"))
      (node (ref "C38") (pin "2") (pinfunction "2_2") (pintype "passive"))
      (node (ref "C39") (pin "1") (pinfunction "1_1") (pintype "passive"))
      (node (ref "C65") (pin "1") (pinfunction "1_1") (pintype "passive"))
      (node (ref "C67") (pin "1") (pinfunction "1_1") (pintype "passive"))
      (node (ref "C68") (pin "1") (pinfunction "1_1") (pintype "passive"))
      (node (ref "C69") (pin "1") (pinfunction "1_1") (pintype "passive"))
      (node (ref "D7") (pin "C") (pinfunction "C_C") (pintype "passive"))
      (node (ref "IC11") (pin "3") (pinfunction "VCC_3") (pintype "power_in"))
      (node (ref "IC5") (pin "8") (pinfunction "V+_8") (pintype "power_in"))
      (node (ref "IC6") (pin "8") (pinfunction "V+_8") (pintype "power_in"))
      (node (ref "IC7") (pin "8") (pinfunction "V+_8") (pintype "power_in"))
      (node (ref "IC8") (pin "8") (pinfunction "V+_8") (pintype "power_in"))
      (node (ref "IC9") (pin "10") (pinfunction "VDD_10") (pintype "power_in"))
      (node (ref "IC9") (pin "25") (pinfunction "VDD_25") (pintype "power_in"))
      (node (ref "IC9") (pin "40") (pinfunction "AVDD_40") (pintype "power_in"))
      (node (ref "IC9") (pin "41") (pinfunction "VDD_41") (pintype "power_in"))
      (node (ref "IC9") (pin "57") (pinfunction "VDD_57") (pintype "power_in"))
      (node (ref "IC9") (pin "9") (pinfunction "AVDD_9") (pintype "power_in"))
      (node (ref "ICSP") (pin "2") (pinfunction "+V_2") (pintype "passive"))
      (node (ref "L4") (pin "2") (pinfunction "2_2") (pintype "passive"))
      (node (ref "R48") (pin "1") (pinfunction "1_1") (pintype "passive"))
      (node (ref "R49") (pin "1") (pinfunction "1_1") (pintype "passive"))
      (node (ref "R50") (pin "1") (pinfunction "1_1") (pintype "passive"))
      (node (ref "R51") (pin "2") (pinfunction "2_2") (pintype "passive"))
      (node (ref "R52") (pin "2") (pinfunction "2_2") (pintype "passive"))
      (node (ref "R53") (pin "1") (pinfunction "1_1") (pintype "passive"))
      (node (ref "R54") (pin "1") (pinfunction "1_1") (pintype "passive"))
      (node (ref "R56") (pin "2") (pinfunction "2_2") (pintype "passive"))
      (node (ref "R57") (pin "2") (pinfunction "2_2") (pintype "passive"))
      (node (ref "SERIAL") (pin "1") (pinfunction "1_1") (pintype "bidirectional"))
      (node (ref "TP9") (pin "1") (pinfunction "P$1_1") (pintype "bidirectional"))
    )
    (net (code "107") (name "VNREG") (class "Default")
      (node (ref "R40") (pin "2") (pinfunction "2_2") (pintype "passive"))
      (node (ref "R42") (pin "1") (pinfunction "1_1") (pintype "passive"))
      (node (ref "R44") (pin "2") (pinfunction "2_2") (pintype "passive"))
      (node (ref "R45") (pin "1") (pinfunction "1_1") (pintype "passive"))
      (node (ref "V_BUS") (pin "31") (pinfunction "31_31") (pintype "passive"))
      (node (ref "V_BUS") (pin "33") (pinfunction "33_33") (pintype "passive"))
      (node (ref "V_BUS") (pin "35") (pinfunction "35_35") (pintype "passive"))
      (node (ref "V_BUS") (pin "37") (pinfunction "37_37") (pintype "passive"))
      (node (ref "V_BUS") (pin "39") (pinfunction "39_39") (pintype "passive"))
    )
    (net (code "108") (name "VOUT_+3V3") (class "Default")
      (node (ref "C18") (pin "2") (pinfunction "2_2") (pintype "passive"))
      (node (ref "IC3") (pin "6") (pinfunction "SENSE_6") (pintype "passive"))
      (node (ref "R33") (pin "2") (pinfunction "2_2") (pintype "passive"))
      (node (ref "R38") (pin "1") (pinfunction "1_1") (pintype "passive"))
      (node (ref "T6") (pin "6") (pinfunction "D_6") (pintype "passive"))
      (node (ref "T6") (pin "7") (pinfunction "D_7") (pintype "passive"))
    )
    (net (code "109") (name "VOUT_+5V") (class "Default")
      (node (ref "C16") (pin "2") (pinfunction "2_2") (pintype "passive"))
      (node (ref "IC2") (pin "6") (pinfunction "SENSE_6") (pintype "passive"))
      (node (ref "R21") (pin "2") (pinfunction "2_2") (pintype "passive"))
      (node (ref "R32") (pin "1") (pinfunction "1_1") (pintype "passive"))
      (node (ref "T4") (pin "6") (pinfunction "D_6") (pintype "passive"))
      (node (ref "T4") (pin "7") (pinfunction "D_7") (pintype "passive"))
    )
    (net (code "110") (name "VOUT_+12V") (class "Default")
      (node (ref "C14") (pin "2") (pinfunction "2_2") (pintype "passive"))
      (node (ref "IC1") (pin "6") (pinfunction "SENSE_6") (pintype "passive"))
      (node (ref "R22") (pin "2") (pinfunction "2_2") (pintype "passive"))
      (node (ref "R27") (pin "1") (pinfunction "1_1") (pintype "passive"))
      (node (ref "T2") (pin "6") (pinfunction "D_6") (pintype "passive"))
      (node (ref "T2") (pin "7") (pinfunction "D_7") (pintype "passive"))
    )
    (net (code "111") (name "VOUT_+NREGV") (class "Default")
      (node (ref "C20") (pin "2") (pinfunction "2_2") (pintype "passive"))
      (node (ref "Q2") (pin "3") (pinfunction "D_3") (pintype "passive"))
      (node (ref "R39") (pin "2") (pinfunction "2_2") (pintype "passive"))
      (node (ref "R44") (pin "1") (pinfunction "1_1") (pintype "passive"))
    )
    (net (code "112") (name "VOUT_3V3") (class "Default")
      (node (ref "C12") (pin "+") (pinfunction "+_+") (pintype "passive"))
      (node (ref "C17") (pin "2") (pinfunction "2_2") (pintype "passive"))
      (node (ref "C61") (pin "2") (pinfunction "2_2") (pintype "passive"))
      (node (ref "IC3") (pin "1") (pinfunction "VIN_1") (pintype "power_in"))
      (node (ref "L2") (pin "2") (pinfunction "2_2") (pintype "passive"))
      (node (ref "R18") (pin "1") (pinfunction "1_1") (pintype "passive"))
      (node (ref "R9") (pin "2") (pinfunction "2_2") (pintype "passive"))
      (node (ref "T5") (pin "7") (pinfunction "D_7") (pintype "passive"))
      (node (ref "TP7") (pin "1") (pinfunction "P$1_1") (pintype "bidirectional"))
    )
    (net (code "113") (name "VOUT_5V") (class "Default")
      (node (ref "C10") (pin "+") (pinfunction "+_+") (pintype "passive"))
      (node (ref "C15") (pin "2") (pinfunction "2_2") (pintype "passive"))
      (node (ref "C59") (pin "2") (pinfunction "2_2") (pintype "passive"))
      (node (ref "IC2") (pin "1") (pinfunction "VIN_1") (pintype "power_in"))
      (node (ref "L3") (pin "2") (pinfunction "2_2") (pintype "passive"))
      (node (ref "R17") (pin "1") (pinfunction "1_1") (pintype "passive"))
      (node (ref "R7") (pin "2") (pinfunction "2_2") (pintype "passive"))
      (node (ref "T3") (pin "7") (pinfunction "D_7") (pintype "passive"))
      (node (ref "TP2") (pin "1") (pinfunction "P$1_1") (pintype "bidirectional"))
    )
    (net (code "114") (name "VOUT_12V") (class "Default")
      (node (ref "C13") (pin "2") (pinfunction "2_2") (pintype "passive"))
      (node (ref "C56") (pin "+") (pinfunction "+_+") (pintype "passive"))
      (node (ref "C57") (pin "+") (pinfunction "+_+") (pintype "passive"))
      (node (ref "C58") (pin "1") (pinfunction "1_1") (pintype "passive"))
      (node (ref "C7") (pin "+") (pinfunction "+_+") (pintype "passive"))
      (node (ref "D6") (pin "C") (pinfunction "C_C") (pintype "passive"))
      (node (ref "IC1") (pin "1") (pinfunction "VIN_1") (pintype "power_in"))
      (node (ref "R14") (pin "2") (pinfunction "2_2") (pintype "passive"))
      (node (ref "R15") (pin "1") (pinfunction "1_1") (pintype "passive"))
      (node (ref "R6") (pin "1") (pinfunction "1_1") (pintype "passive"))
      (node (ref "T1") (pin "7") (pinfunction "D_7") (pintype "passive"))
      (node (ref "TP11") (pin "1") (pinfunction "P$1_1") (pintype "bidirectional"))
    )
    (net (code "115") (name "VOUT_BACKUP_3V3") (class "Default")
      (node (ref "BACKUP") (pin "10") (pinfunction "10_10") (pintype "passive"))
      (node (ref "BACKUP") (pin "11") (pinfunction "11_11") (pintype "passive"))
      (node (ref "BACKUP") (pin "12") (pinfunction "12_12") (pintype "passive"))
      (node (ref "BACKUP") (pin "9") (pinfunction "9_9") (pintype "passive"))
      (node (ref "R65") (pin "1") (pinfunction "1_1") (pintype "passive"))
      (node (ref "T5") (pin "6") (pinfunction "D_6") (pintype "passive"))
      (node (ref "TP25") (pin "1") (pinfunction "P$1_1") (pintype "bidirectional"))
    )
    (net (code "116") (name "VOUT_BACKUP_5V") (class "Default")
      (node (ref "BACKUP") (pin "5") (pinfunction "5_5") (pintype "passive"))
      (node (ref "BACKUP") (pin "6") (pinfunction "6_6") (pintype "passive"))
      (node (ref "BACKUP") (pin "7") (pinfunction "7_7") (pintype "passive"))
      (node (ref "BACKUP") (pin "8") (pinfunction "8_8") (pintype "passive"))
      (node (ref "R62") (pin "1") (pinfunction "1_1") (pintype "passive"))
      (node (ref "T3") (pin "6") (pinfunction "D_6") (pintype "passive"))
      (node (ref "TP3") (pin "1") (pinfunction "P$1_1") (pintype "bidirectional"))
    )
    (net (code "117") (name "VOUT_BACKUP_12V") (class "Default")
      (node (ref "BACKUP") (pin "1") (pinfunction "1_1") (pintype "passive"))
      (node (ref "BACKUP") (pin "2") (pinfunction "2_2") (pintype "passive"))
      (node (ref "BACKUP") (pin "3") (pinfunction "3_3") (pintype "passive"))
      (node (ref "BACKUP") (pin "4") (pinfunction "4_4") (pintype "passive"))
      (node (ref "R61") (pin "1") (pinfunction "1_1") (pintype "passive"))
      (node (ref "T1") (pin "6") (pinfunction "D_6") (pintype "passive"))
      (node (ref "TP5") (pin "1") (pinfunction "P$1_1") (pintype "bidirectional"))
    )
    (net (code "118") (name "unconnected-(CAN-Pad1)") (class "Default")
      (node (ref "CAN") (pin "1") (pinfunction "1_1") (pintype "bidirectional"))
    )
    (net (code "119") (name "unconnected-(IC4-STAT-Pad4)") (class "Default")
      (node (ref "IC4") (pin "4") (pinfunction "STAT_4") (pintype "passive"))
    )
    (net (code "120") (name "unconnected-(IC9-RB5{slash}T0CKI{slash}T3CKI{slash}CCP5{slash}KBI1-Pad21)") (class "Default")
      (node (ref "IC9") (pin "21") (pinfunction "RB5/T0CKI/T3CKI/CCP5/KBI1_21") (pintype "bidirectional"))
    )
    (net (code "121") (name "unconnected-(IC9-RC0{slash}SOSCO{slash}SCLKI-Pad48)") (class "Default")
      (node (ref "IC9") (pin "48") (pinfunction "RC0/SOSCO/SCLKI_48") (pintype "bidirectional"))
    )
    (net (code "122") (name "unconnected-(IC9-RC4{slash}SDA{slash}SDI-Pad62)") (class "Default")
      (node (ref "IC9") (pin "62") (pinfunction "RC4/SDA/SDI_62") (pintype "bidirectional"))
    )
    (net (code "123") (name "unconnected-(IC9-RC5{slash}SDO-Pad63)") (class "Default")
      (node (ref "IC9") (pin "63") (pinfunction "RC5/SDO_63") (pintype "bidirectional"))
    )
    (net (code "124") (name "unconnected-(IC9-RC6{slash}CCP3-Pad64)") (class "Default")
      (node (ref "IC9") (pin "64") (pinfunction "RC6/CCP3_64") (pintype "bidirectional"))
    )
    (net (code "125") (name "unconnected-(IC9-RD3{slash}C2INB{slash}CTMUI{slash}PSP3-Pad59)") (class "Default")
      (node (ref "IC9") (pin "59") (pinfunction "RD3/C2INB/CTMUI/PSP3_59") (pintype "bidirectional"))
    )
    (net (code "126") (name "unconnected-(IC9-RD5{slash}P1B{slash}PSP5-Pad3)") (class "Default")
      (node (ref "IC9") (pin "3") (pinfunction "RD5/P1B/PSP5_3") (pintype "bidirectional"))
    )
    (net (code "127") (name "unconnected-(IC9-RD6{slash}P1C{slash}PSP6-Pad4)") (class "Default")
      (node (ref "IC9") (pin "4") (pinfunction "RD6/P1C/PSP6_4") (pintype "bidirectional"))
    )
    (net (code "128") (name "unconnected-(IC9-RD7{slash}P1D{slash}PSP7-Pad5)") (class "Default")
      (node (ref "IC9") (pin "5") (pinfunction "RD7/P1D/PSP7_5") (pintype "bidirectional"))
    )
    (net (code "129") (name "unconnected-(IC9-RE4{slash}CANRX-Pad27)") (class "Default")
      (node (ref "IC9") (pin "27") (pinfunction "RE4/CANRX_27") (pintype "bidirectional"))
    )
    (net (code "130") (name "unconnected-(IC9-RE5{slash}CANTX-Pad24)") (class "Default")
      (node (ref "IC9") (pin "24") (pinfunction "RE5/CANTX_24") (pintype "bidirectional"))
    )
    (net (code "131") (name "unconnected-(IC9-RE6{slash}RX2{slash}DT2-Pad60)") (class "Default")
      (node (ref "IC9") (pin "60") (pinfunction "RE6/RX2/DT2_60") (pintype "bidirectional"))
    )
    (net (code "132") (name "unconnected-(IC9-RE7{slash}TX2{slash}CK2-Pad61)") (class "Default")
      (node (ref "IC9") (pin "61") (pinfunction "RE7/TX2/CK2_61") (pintype "bidirectional"))
    )
    (net (code "133") (name "unconnected-(IC9-RF2{slash}MDCIN1-Pad35)") (class "Default")
      (node (ref "IC9") (pin "35") (pinfunction "RF2/MDCIN1_35") (pintype "bidirectional"))
    )
    (net (code "134") (name "unconnected-(IC9-RF3-Pad36)") (class "Default")
      (node (ref "IC9") (pin "36") (pinfunction "RF3_36") (pintype "bidirectional"))
    )
    (net (code "135") (name "unconnected-(IC9-RF4{slash}MDCIN2-Pad44)") (class "Default")
      (node (ref "IC9") (pin "44") (pinfunction "RF4/MDCIN2_44") (pintype "bidirectional"))
    )
    (net (code "136") (name "unconnected-(IC9-RF5-Pad45)") (class "Default")
      (node (ref "IC9") (pin "45") (pinfunction "RF5_45") (pintype "bidirectional"))
    )
    (net (code "137") (name "unconnected-(IC9-RF6{slash}MDOUT-Pad52)") (class "Default")
      (node (ref "IC9") (pin "52") (pinfunction "RF6/MDOUT_52") (pintype "bidirectional"))
    )
    (net (code "138") (name "unconnected-(IC9-RF7-Pad53)") (class "Default")
      (node (ref "IC9") (pin "53") (pinfunction "RF7_53") (pintype "bidirectional"))
    )
    (net (code "139") (name "unconnected-(IC9-RG1{slash}CANTX2-Pad7)") (class "Default")
      (node (ref "IC9") (pin "7") (pinfunction "RG1/CANTX2_7") (pintype "bidirectional"))
    )
    (net (code "140") (name "unconnected-(IC9-RG2{slash}T3CKI-Pad11)") (class "Default")
      (node (ref "IC9") (pin "11") (pinfunction "RG2/T3CKI_11") (pintype "bidirectional"))
    )
    (net (code "141") (name "unconnected-(IC11-VREF-Pad5)") (class "Default")
      (node (ref "IC11") (pin "5") (pinfunction "VREF_5") (pintype "input"))
    )
    (net (code "142") (name "unconnected-(T1A-D2-Pad8)") (class "Default")
      (node (ref "T1") (pin "8") (pinfunction "D2_8") (pintype "passive"))
    )
    (net (code "143") (name "unconnected-(T1B-D2-Pad5)") (class "Default")
      (node (ref "T1") (pin "5") (pinfunction "D2_5") (pintype "passive"))
    )
    (net (code "144") (name "unconnected-(T2A-D2-Pad8)") (class "Default")
      (node (ref "T2") (pin "8") (pinfunction "D2_8") (pintype "passive"))
    )
    (net (code "145") (name "unconnected-(T2B-D2-Pad5)") (class "Default")
      (node (ref "T2") (pin "5") (pinfunction "D2_5") (pintype "passive"))
    )
    (net (code "146") (name "unconnected-(T3A-D2-Pad8)") (class "Default")
      (node (ref "T3") (pin "8") (pinfunction "D2_8") (pintype "passive"))
    )
    (net (code "147") (name "unconnected-(T3B-D2-Pad5)") (class "Default")
      (node (ref "T3") (pin "5") (pinfunction "D2_5") (pintype "passive"))
    )
    (net (code "148") (name "unconnected-(T4A-D2-Pad8)") (class "Default")
      (node (ref "T4") (pin "8") (pinfunction "D2_8") (pintype "passive"))
    )
    (net (code "149") (name "unconnected-(T4B-D2-Pad5)") (class "Default")
      (node (ref "T4") (pin "5") (pinfunction "D2_5") (pintype "passive"))
    )
    (net (code "150") (name "unconnected-(T5A-D2-Pad8)") (class "Default")
      (node (ref "T5") (pin "8") (pinfunction "D2_8") (pintype "passive"))
    )
    (net (code "151") (name "unconnected-(T5B-D2-Pad5)") (class "Default")
      (node (ref "T5") (pin "5") (pinfunction "D2_5") (pintype "passive"))
    )
    (net (code "152") (name "unconnected-(T6A-D2-Pad8)") (class "Default")
      (node (ref "T6") (pin "8") (pinfunction "D2_8") (pintype "passive"))
    )
    (net (code "153") (name "unconnected-(T6B-D2-Pad5)") (class "Default")
      (node (ref "T6") (pin "5") (pinfunction "D2_5") (pintype "passive"))
    )
    (net (code "154") (name "~{MCLR}") (class "Default")
      (node (ref "IC9") (pin "28") (pinfunction "~{MCLR/}RE3_28") (pintype "bidirectional"))
      (node (ref "ICSP") (pin "1") (pinfunction "/MCLR_1") (pintype "passive"))
      (node (ref "R47") (pin "2") (pinfunction "2_2") (pintype "passive"))
    )
  )
)
